# FPGA-ArduinoR3.net
KiCad netlist of a schematic drawn in EAGLE
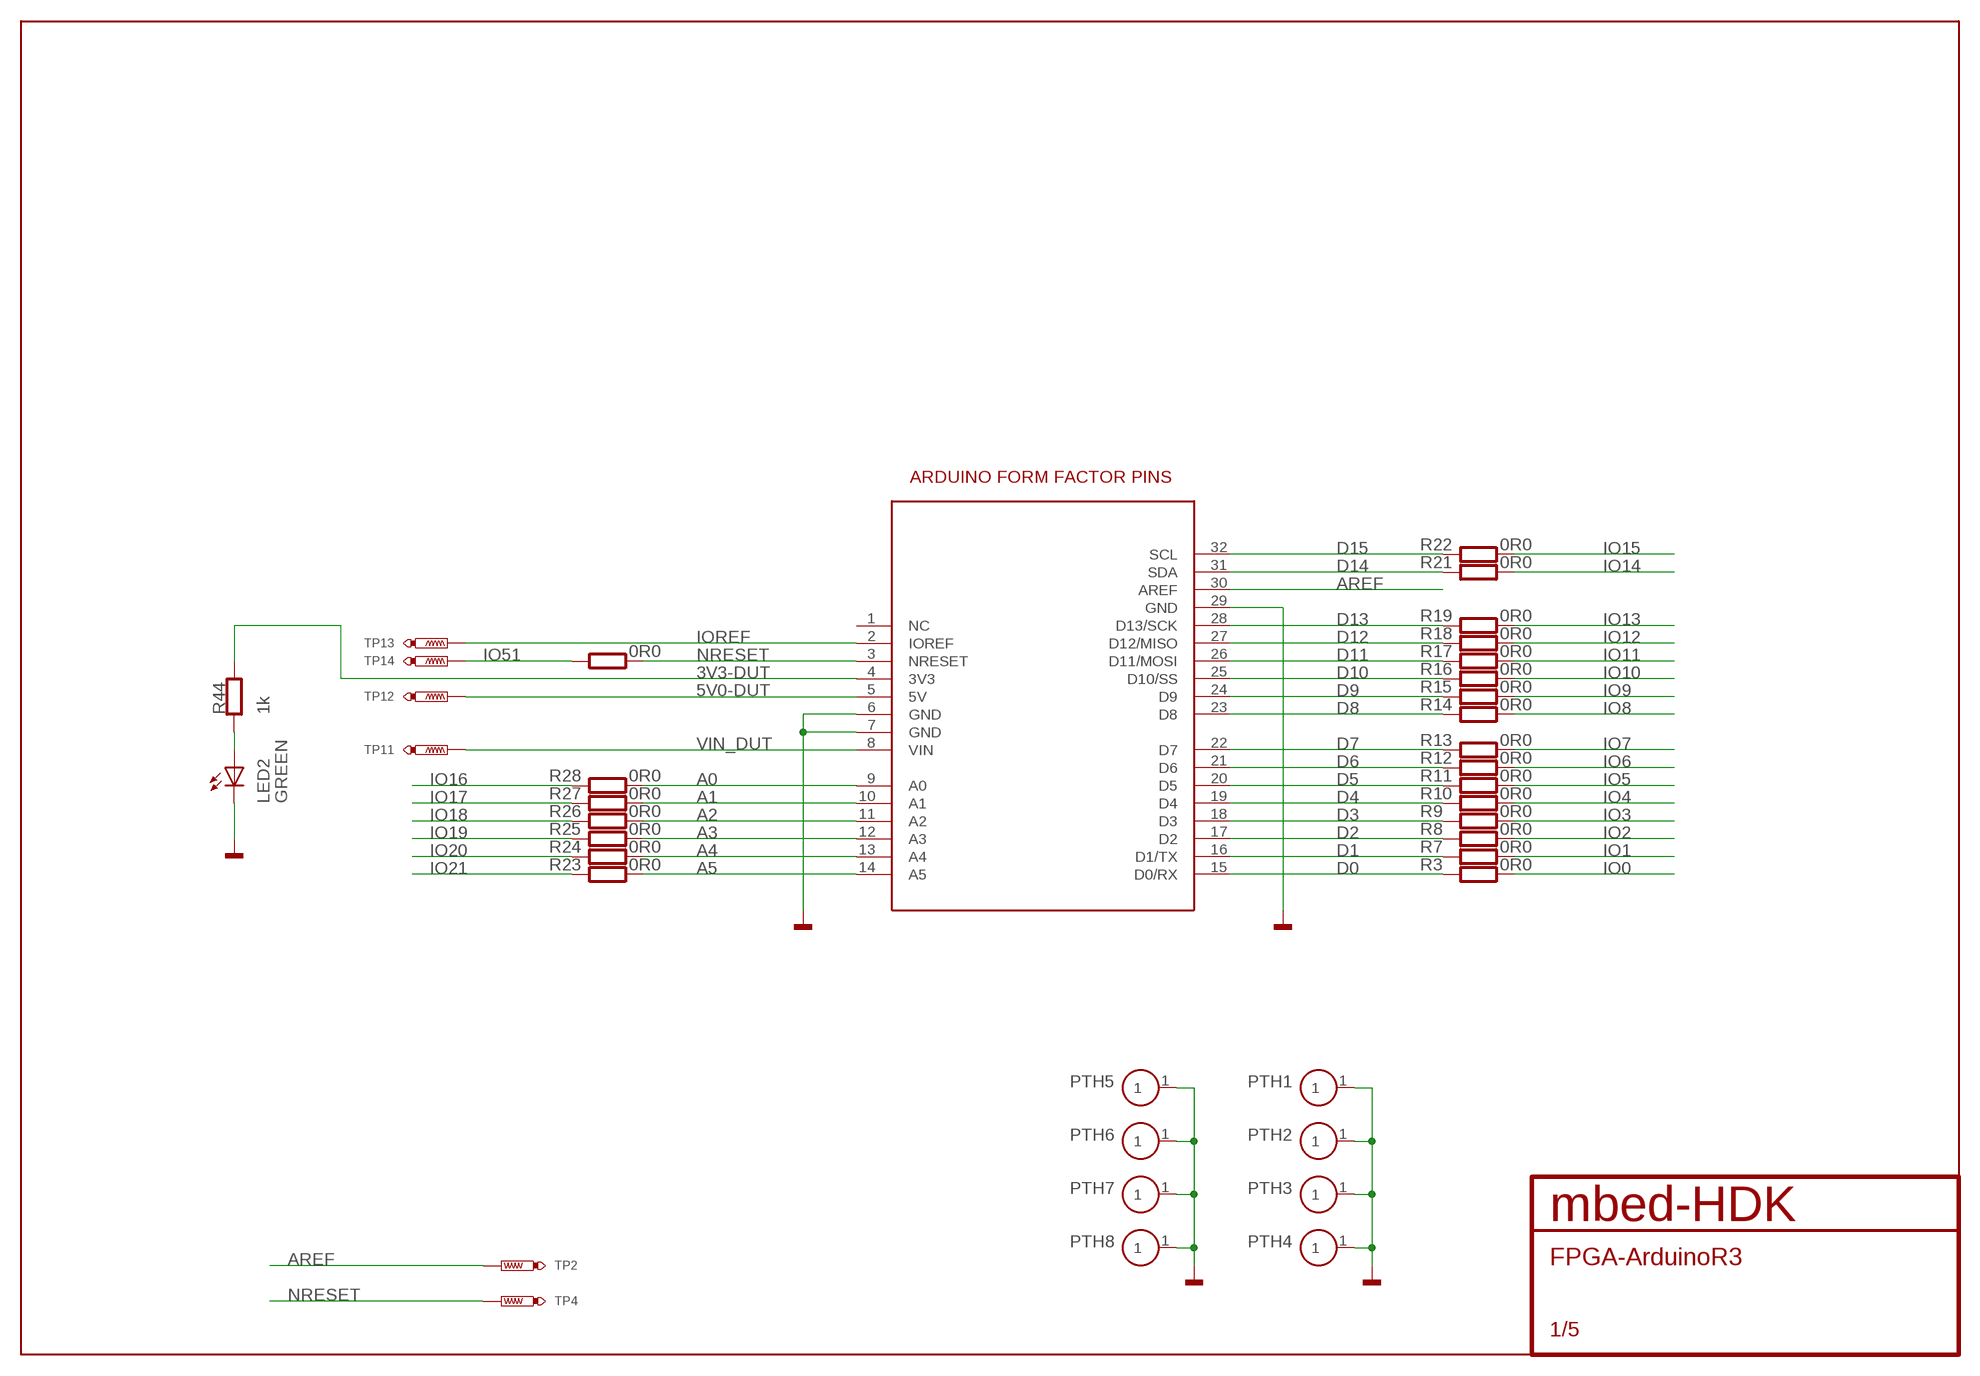
[diagram p0: schematic, sheet 1]
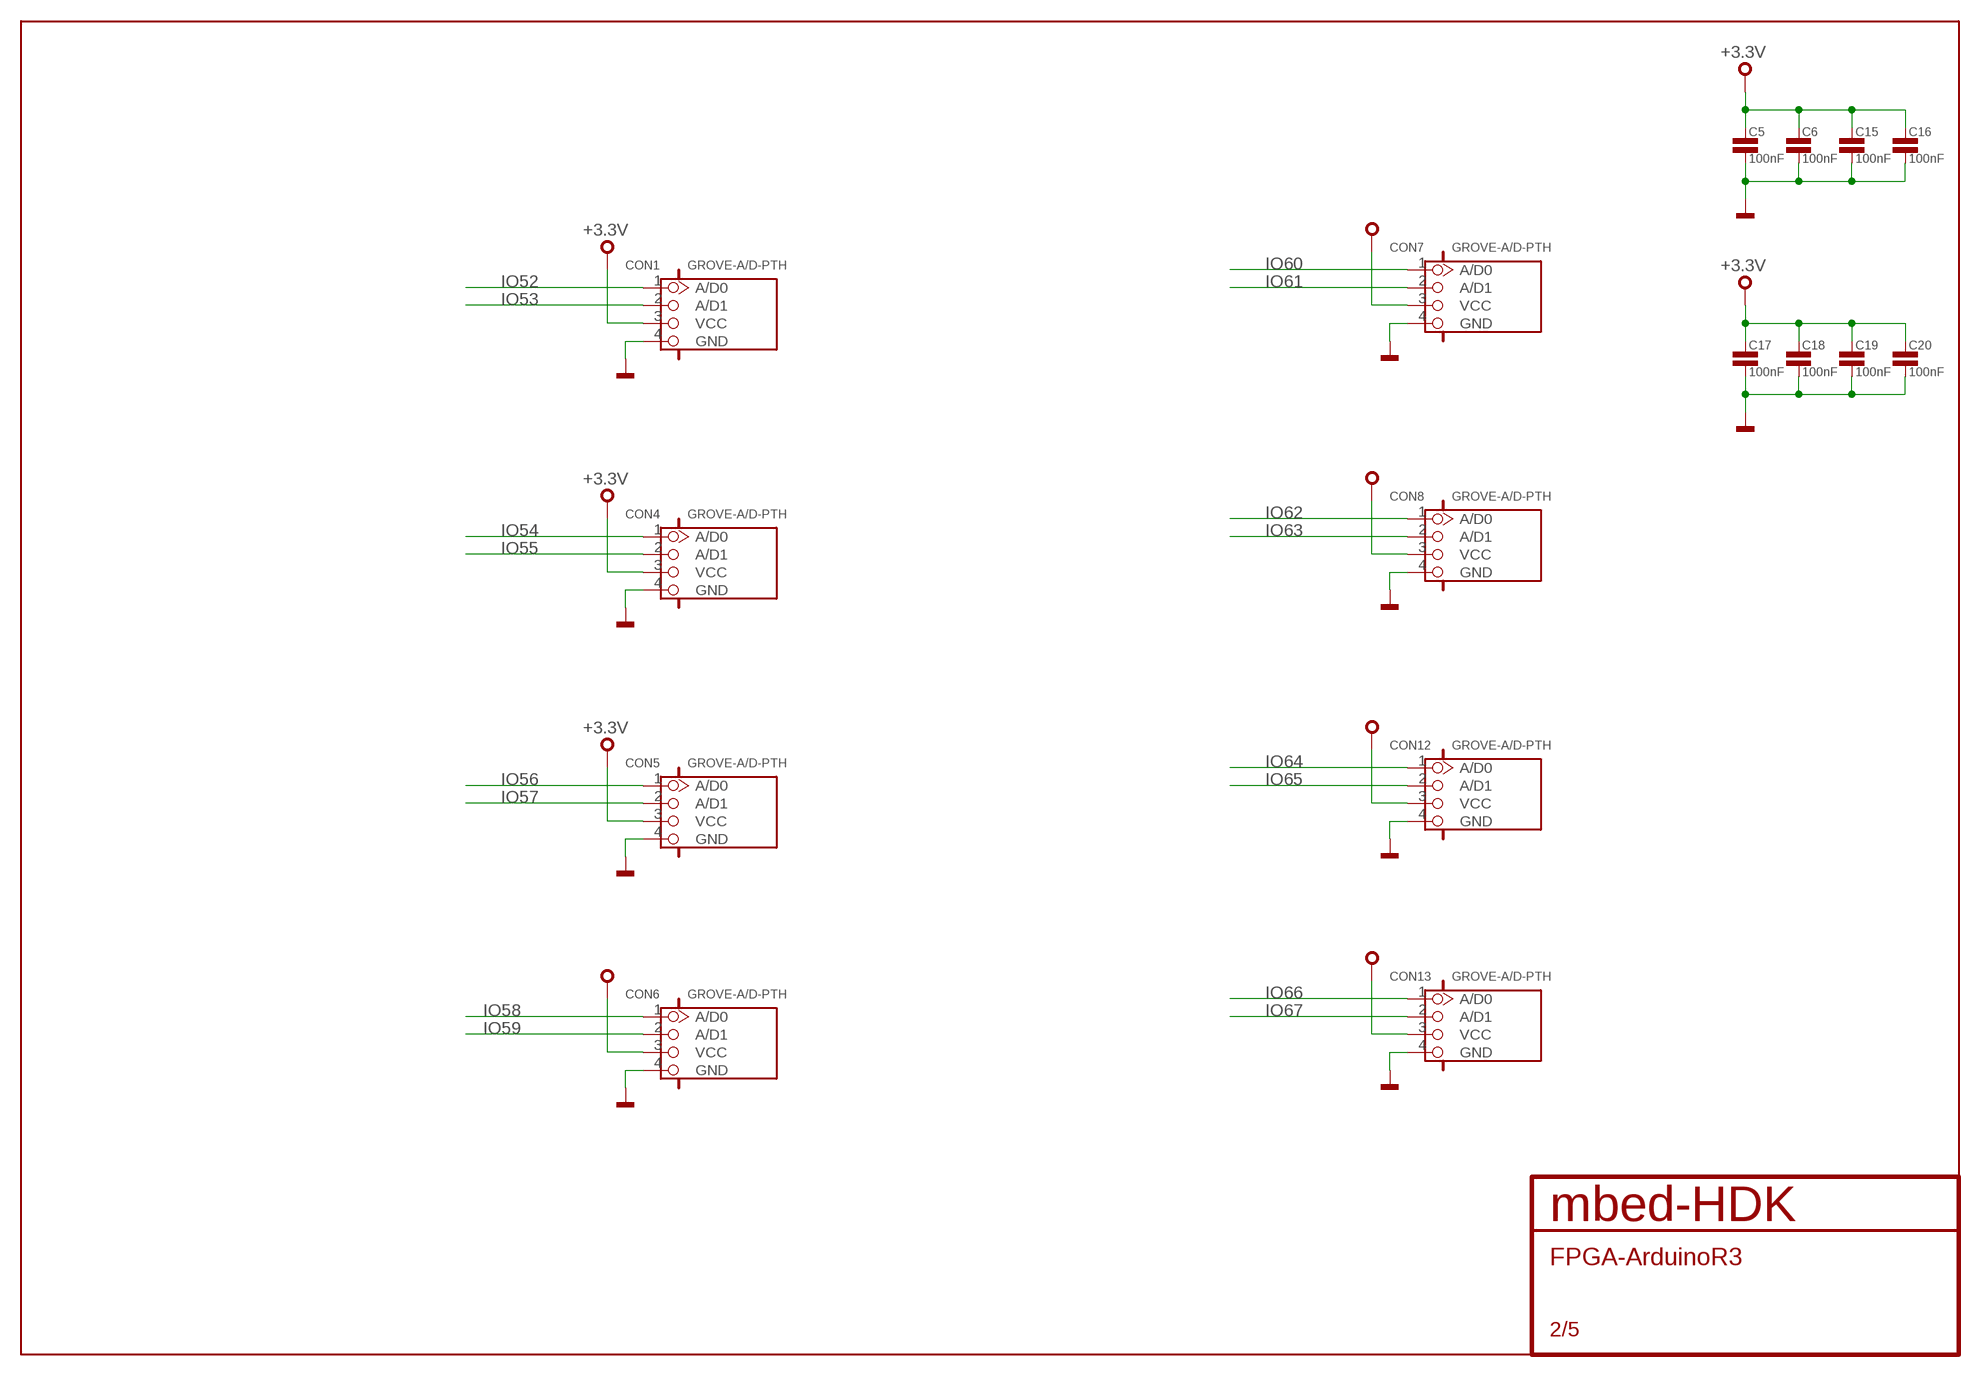
[diagram p1: schematic, sheet 2]
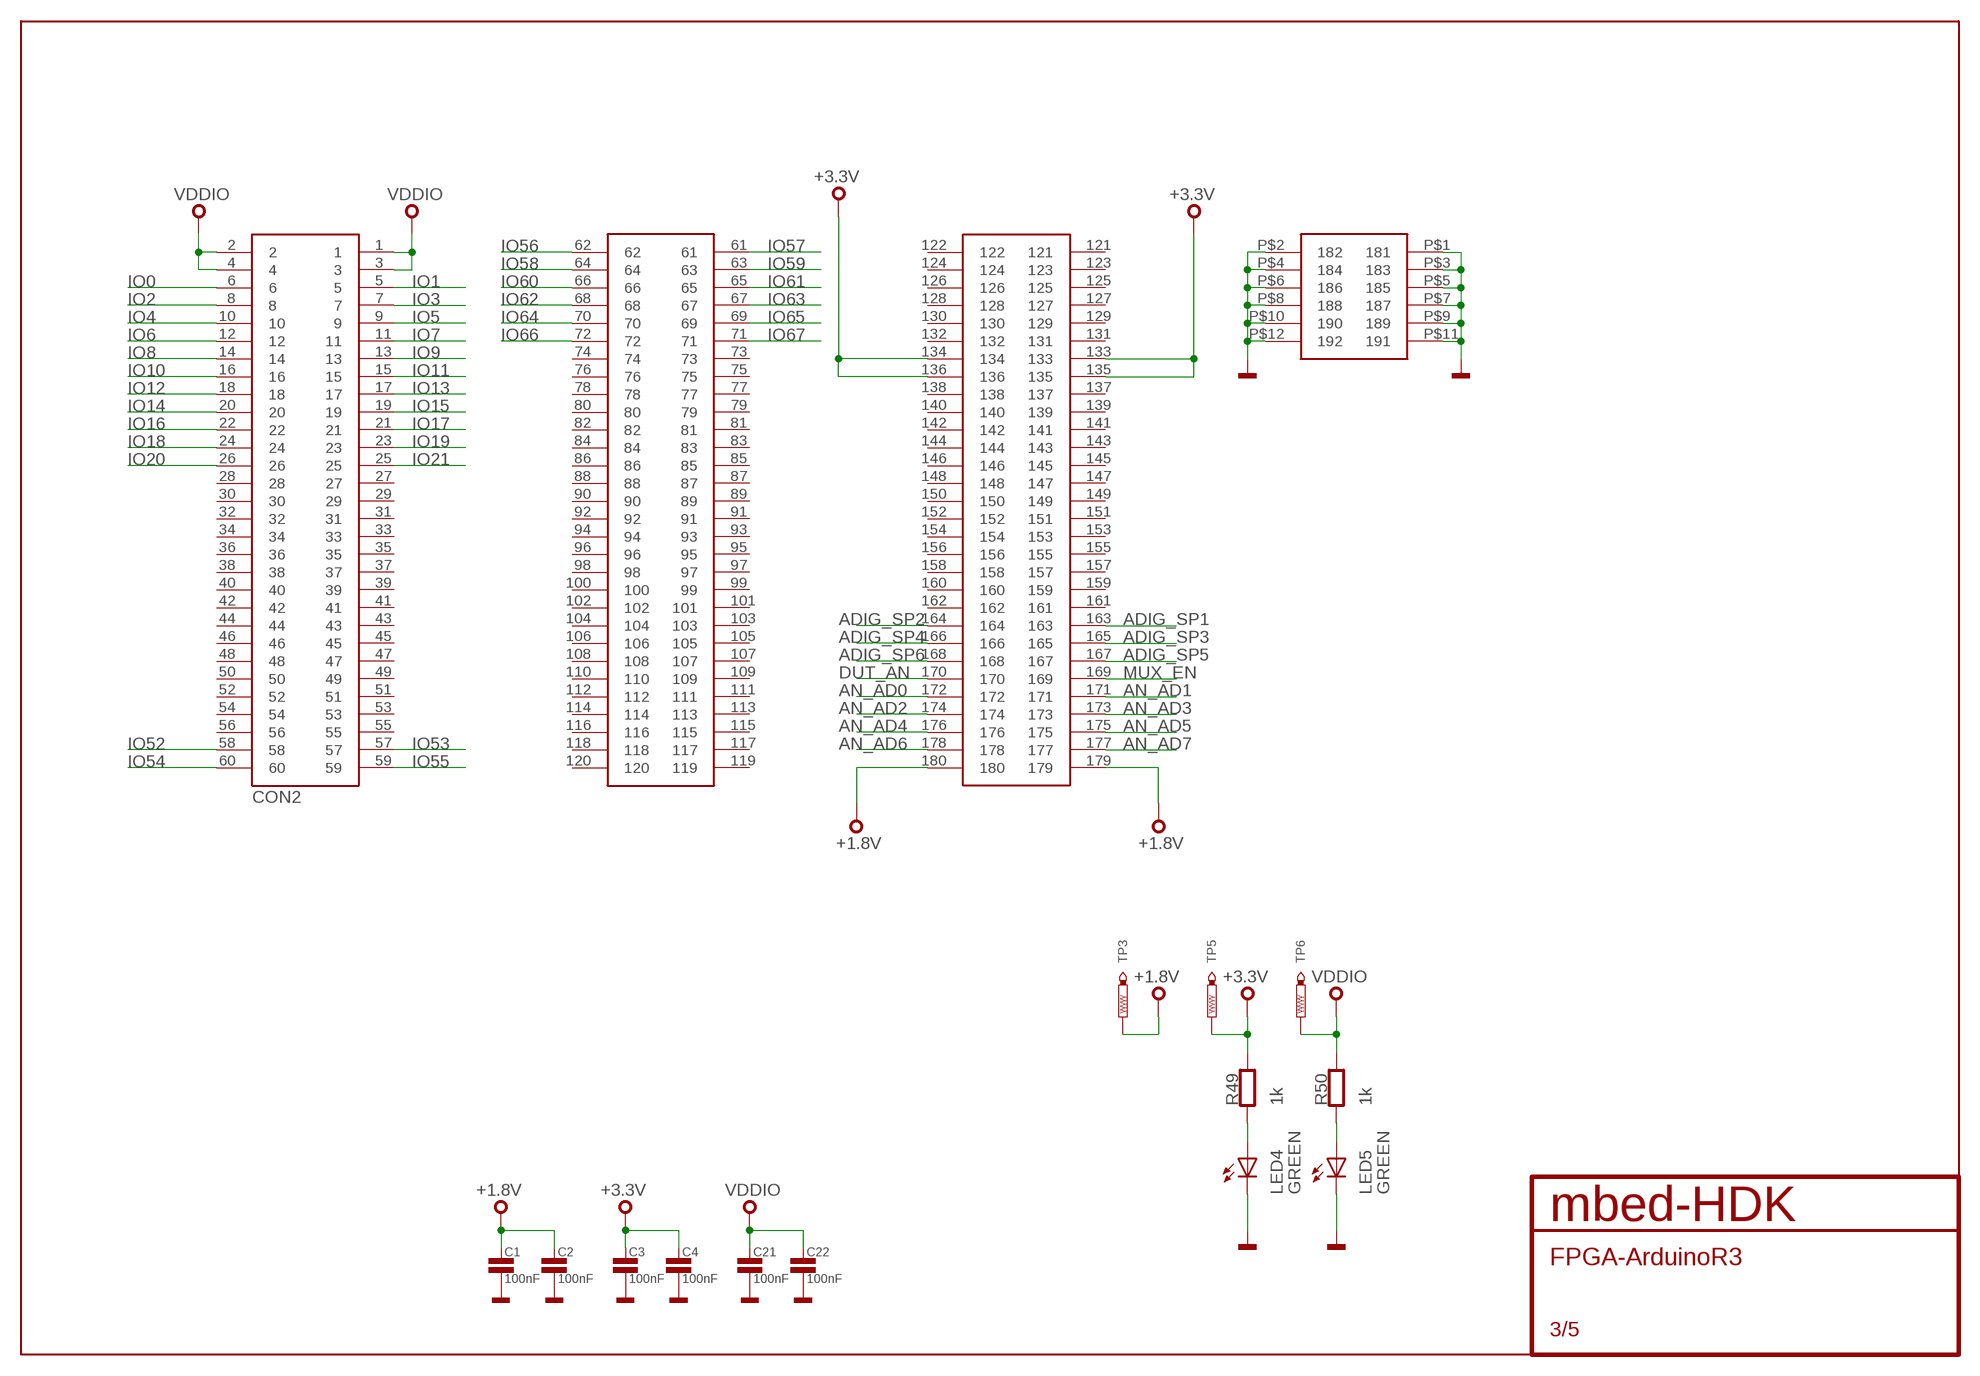
[diagram p2: schematic, sheet 3]
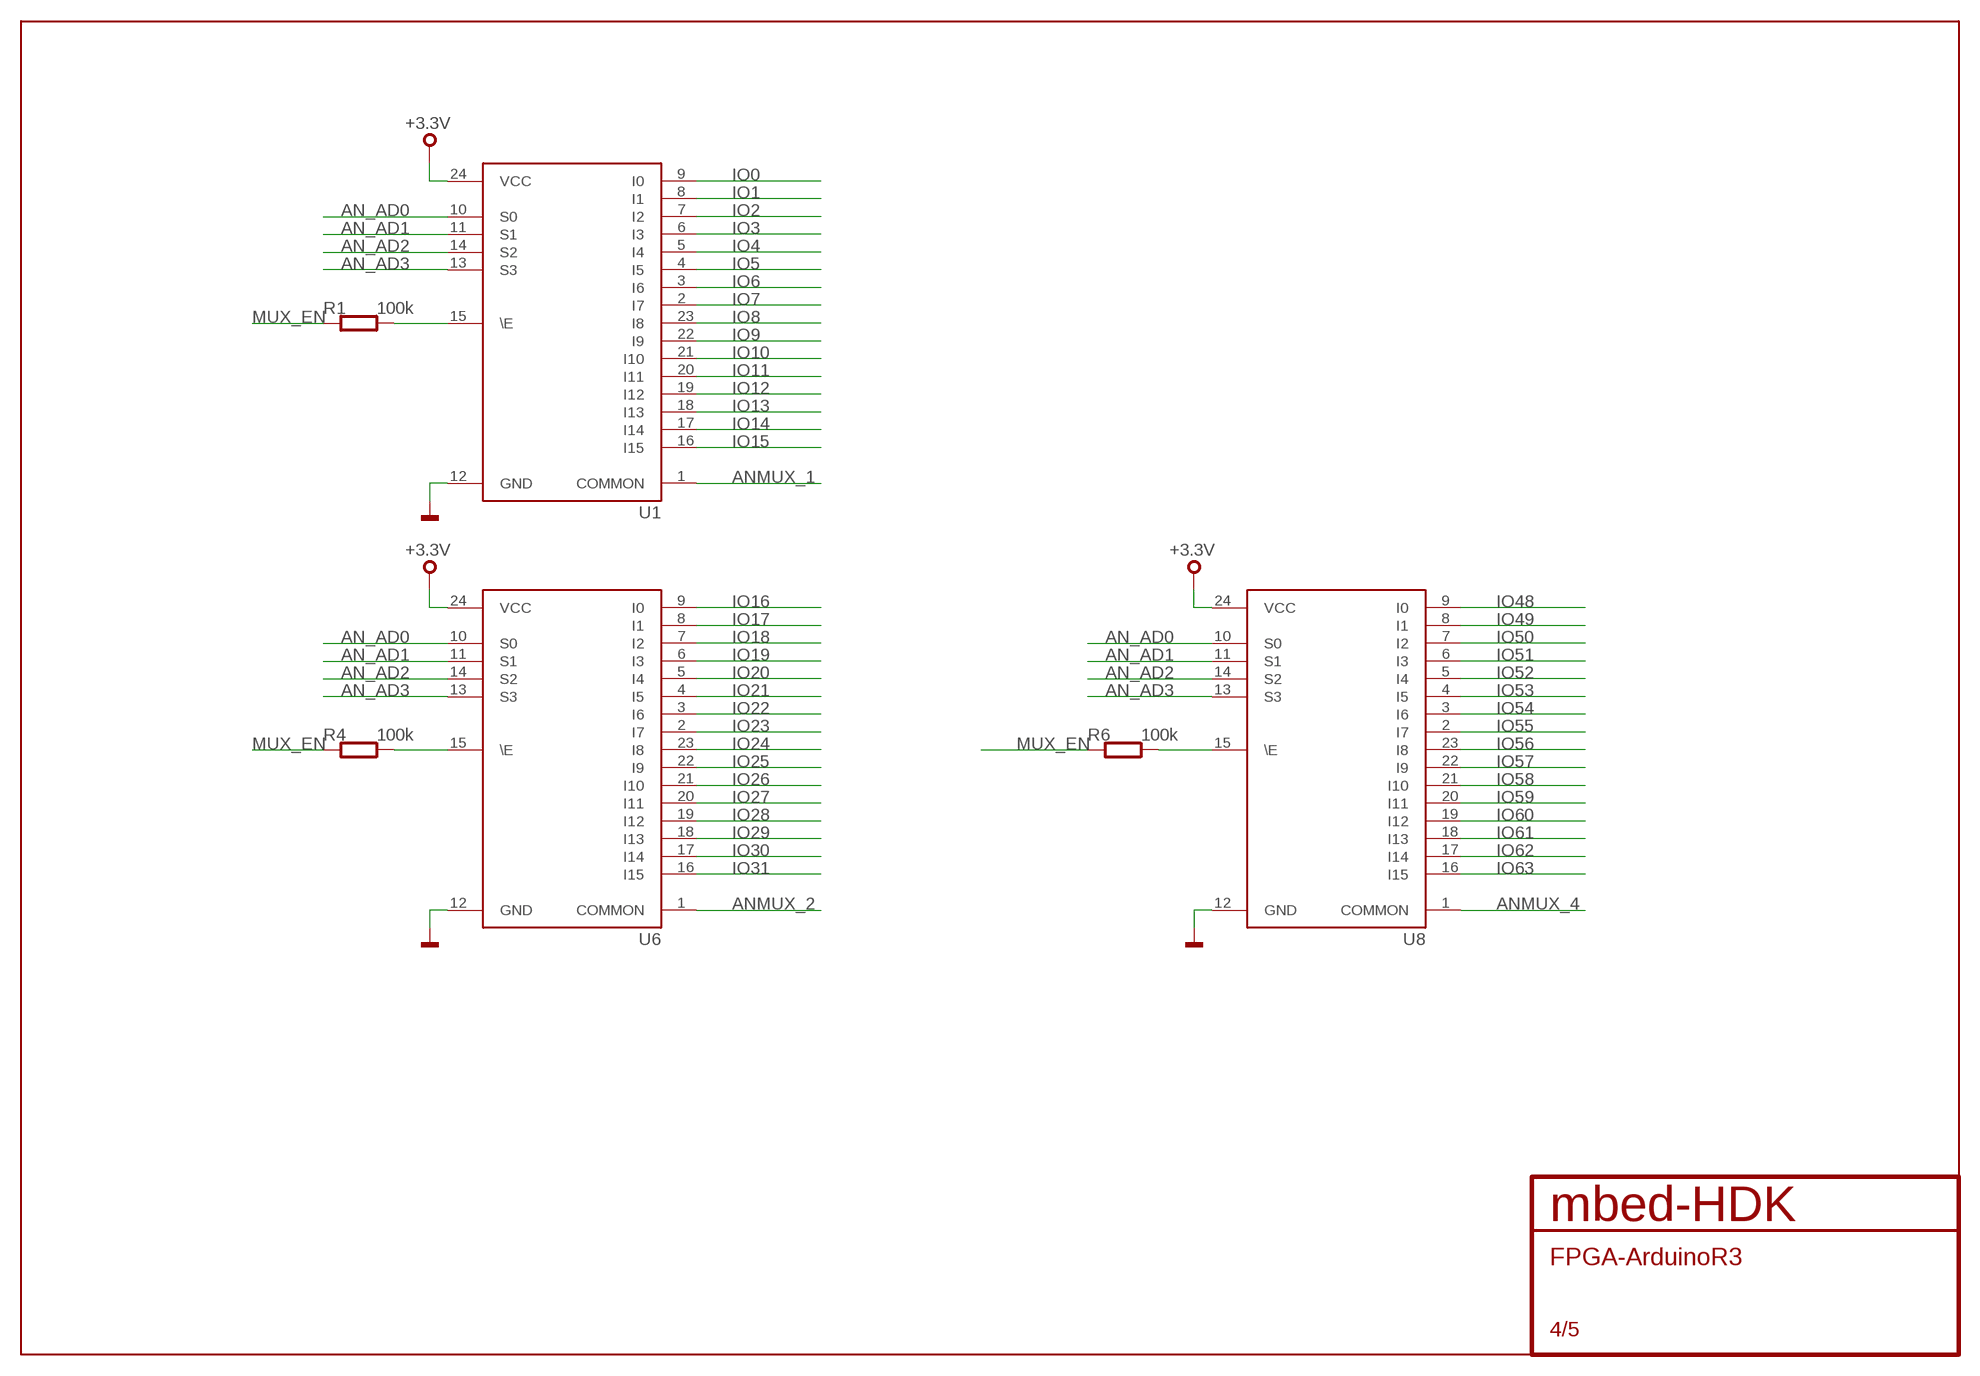
[diagram p3: schematic, sheet 4]
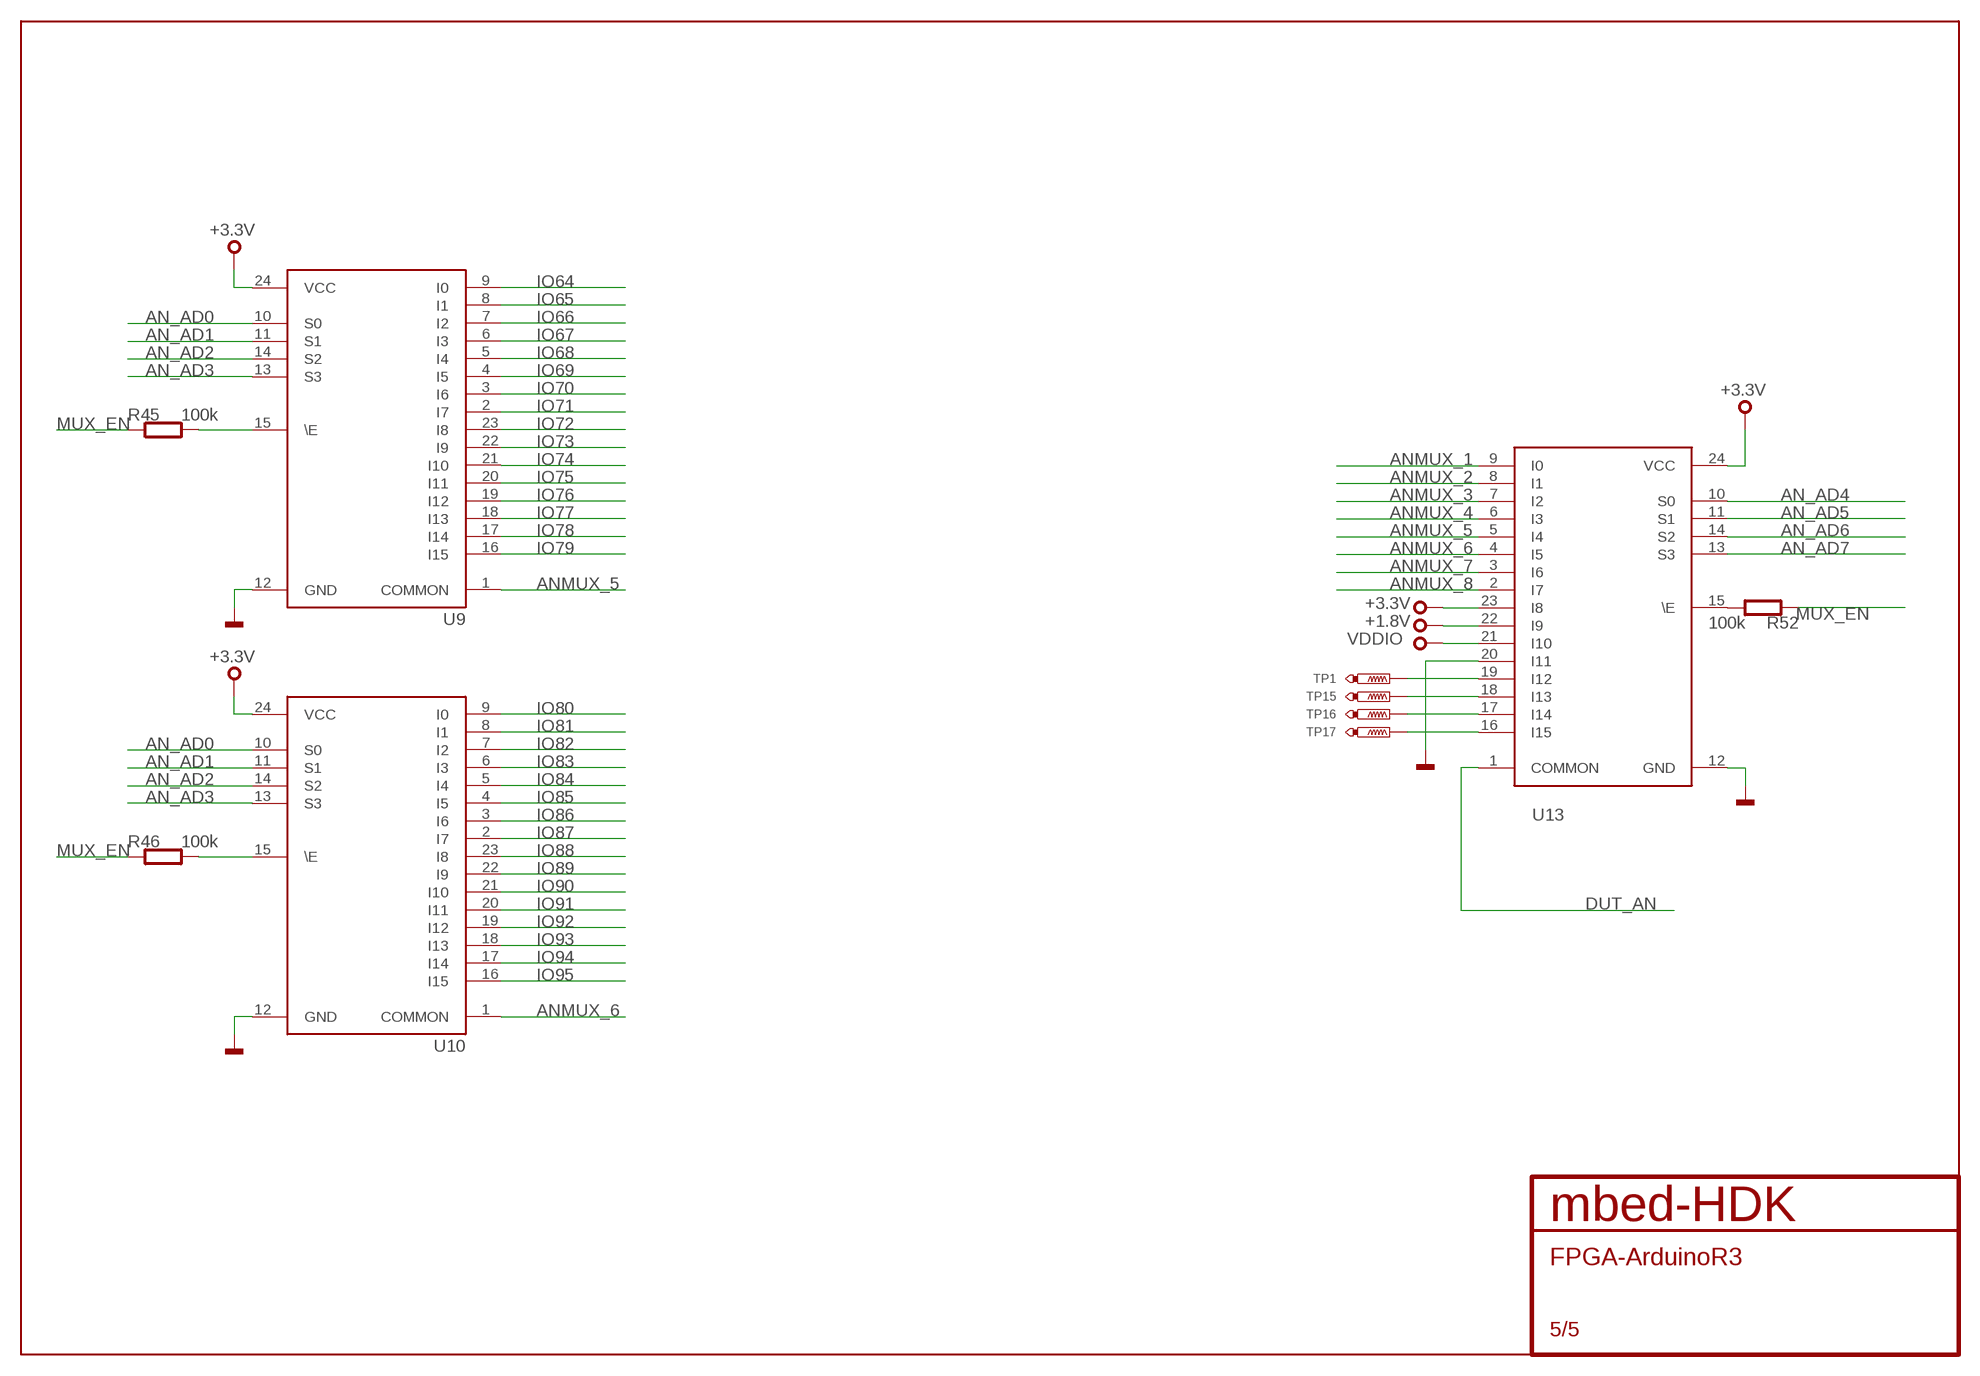
[diagram p4: schematic, sheet 5]

(export (version "E")
  (design (tool "Eeschema 10.0.6"))
  (components
    (comp (ref "R1")
      (value "100k")
      (footprint "eagle-import:0603")
      (libsource (lib "eagle-import") (part "R0603"))
    )
    (comp (ref "R4")
      (value "100k")
      (footprint "eagle-import:0603")
      (libsource (lib "eagle-import") (part "R0603"))
    )
    (comp (ref "R6")
      (value "100k")
      (footprint "eagle-import:0603")
      (libsource (lib "eagle-import") (part "R0603"))
    )
    (comp (ref "U1")
      (value "CD74HCT4067")
      (footprint "eagle-import:SO24")
      (libsource (lib "eagle-import") (part "CD74HCT4067"))
    )
    (comp (ref "U6")
      (value "CD74HCT4067")
      (footprint "eagle-import:SO24")
      (libsource (lib "eagle-import") (part "CD74HCT4067"))
    )
    (comp (ref "U8")
      (value "CD74HCT4067")
      (footprint "eagle-import:SO24")
      (libsource (lib "eagle-import") (part "CD74HCT4067"))
    )
    (comp (ref "C1")
      (value "100nF")
      (footprint "eagle-import:0603")
      (libsource (lib "eagle-import") (part "C0603"))
    )
    (comp (ref "C2")
      (value "100nF")
      (footprint "eagle-import:0603")
      (libsource (lib "eagle-import") (part "C0603"))
    )
    (comp (ref "C3")
      (value "100nF")
      (footprint "eagle-import:0603")
      (libsource (lib "eagle-import") (part "C0603"))
    )
    (comp (ref "C4")
      (value "100nF")
      (footprint "eagle-import:0603")
      (libsource (lib "eagle-import") (part "C0603"))
    )
    (comp (ref "C21")
      (value "100nF")
      (footprint "eagle-import:0603")
      (libsource (lib "eagle-import") (part "C0603"))
    )
    (comp (ref "C22")
      (value "100nF")
      (footprint "eagle-import:0603")
      (libsource (lib "eagle-import") (part "C0603"))
    )
    (comp (ref "CON2")
      (value "QSH-090-01-L-D-A")
      (footprint "eagle-import:QSH-090-01-L-D-A")
      (libsource (lib "eagle-import") (part "QSH-090-01-L-D-A"))
    )
    (comp (ref "LED4")
      (value "GREEN")
      (footprint "eagle-import:CHIPLED_0603")
      (libsource (lib "eagle-import") (part "LED0603"))
    )
    (comp (ref "LED5")
      (value "GREEN")
      (footprint "eagle-import:CHIPLED_0603")
      (libsource (lib "eagle-import") (part "LED0603"))
    )
    (comp (ref "R49")
      (value "1k")
      (footprint "eagle-import:0603")
      (libsource (lib "eagle-import") (part "R0603"))
    )
    (comp (ref "R50")
      (value "1k")
      (footprint "eagle-import:0603")
      (libsource (lib "eagle-import") (part "R0603"))
    )
    (comp (ref "TP3")
      (value "TEST_POINT-50R-PTH")
      (footprint "eagle-import:TP50-PTH")
      (libsource (lib "eagle-import") (part "TEST_POINT-50R-PTH"))
    )
    (comp (ref "TP5")
      (value "TEST_POINT-50R-PTH")
      (footprint "eagle-import:TP50-PTH")
      (libsource (lib "eagle-import") (part "TEST_POINT-50R-PTH"))
    )
    (comp (ref "TP6")
      (value "TEST_POINT-50R-PTH")
      (footprint "eagle-import:TP50-PTH")
      (libsource (lib "eagle-import") (part "TEST_POINT-50R-PTH"))
    )
    (comp (ref "C5")
      (value "100nF")
      (footprint "eagle-import:0603")
      (libsource (lib "eagle-import") (part "C0603"))
    )
    (comp (ref "C6")
      (value "100nF")
      (footprint "eagle-import:0603")
      (libsource (lib "eagle-import") (part "C0603"))
    )
    (comp (ref "C15")
      (value "100nF")
      (footprint "eagle-import:0603")
      (libsource (lib "eagle-import") (part "C0603"))
    )
    (comp (ref "C16")
      (value "100nF")
      (footprint "eagle-import:0603")
      (libsource (lib "eagle-import") (part "C0603"))
    )
    (comp (ref "C17")
      (value "100nF")
      (footprint "eagle-import:0603")
      (libsource (lib "eagle-import") (part "C0603"))
    )
    (comp (ref "C18")
      (value "100nF")
      (footprint "eagle-import:0603")
      (libsource (lib "eagle-import") (part "C0603"))
    )
    (comp (ref "C19")
      (value "100nF")
      (footprint "eagle-import:0603")
      (libsource (lib "eagle-import") (part "C0603"))
    )
    (comp (ref "C20")
      (value "100nF")
      (footprint "eagle-import:0603")
      (libsource (lib "eagle-import") (part "C0603"))
    )
    (comp (ref "CON1")
      (value "GROVE-A/D-PTH")
      (footprint "eagle-import:HW4-2.0")
      (libsource (lib "eagle-import") (part "GROVE-A/D-PTH"))
    )
    (comp (ref "CON4")
      (value "GROVE-A/D-PTH")
      (footprint "eagle-import:HW4-2.0")
      (libsource (lib "eagle-import") (part "GROVE-A/D-PTH"))
    )
    (comp (ref "CON5")
      (value "GROVE-A/D-PTH")
      (footprint "eagle-import:HW4-2.0")
      (libsource (lib "eagle-import") (part "GROVE-A/D-PTH"))
    )
    (comp (ref "CON6")
      (value "GROVE-A/D-PTH")
      (footprint "eagle-import:HW4-2.0")
      (libsource (lib "eagle-import") (part "GROVE-A/D-PTH"))
    )
    (comp (ref "CON7")
      (value "GROVE-A/D-PTH")
      (footprint "eagle-import:HW4-2.0")
      (libsource (lib "eagle-import") (part "GROVE-A/D-PTH"))
    )
    (comp (ref "CON8")
      (value "GROVE-A/D-PTH")
      (footprint "eagle-import:HW4-2.0")
      (libsource (lib "eagle-import") (part "GROVE-A/D-PTH"))
    )
    (comp (ref "CON12")
      (value "GROVE-A/D-PTH")
      (footprint "eagle-import:HW4-2.0")
      (libsource (lib "eagle-import") (part "GROVE-A/D-PTH"))
    )
    (comp (ref "CON13")
      (value "GROVE-A/D-PTH")
      (footprint "eagle-import:HW4-2.0")
      (libsource (lib "eagle-import") (part "GROVE-A/D-PTH"))
    )
    (comp (ref "R45")
      (value "100k")
      (footprint "eagle-import:0603")
      (libsource (lib "eagle-import") (part "R0603"))
    )
    (comp (ref "R46")
      (value "100k")
      (footprint "eagle-import:0603")
      (libsource (lib "eagle-import") (part "R0603"))
    )
    (comp (ref "R52")
      (value "100k")
      (footprint "eagle-import:0603")
      (libsource (lib "eagle-import") (part "R0603"))
    )
    (comp (ref "TP1")
      (value "TEST_POINT-50R-PTH")
      (footprint "eagle-import:TP50-PTH")
      (libsource (lib "eagle-import") (part "TEST_POINT-50R-PTH"))
    )
    (comp (ref "TP15")
      (value "TEST_POINT-50R-PTH")
      (footprint "eagle-import:TP50-PTH")
      (libsource (lib "eagle-import") (part "TEST_POINT-50R-PTH"))
    )
    (comp (ref "TP16")
      (value "TEST_POINT-50R-PTH")
      (footprint "eagle-import:TP50-PTH")
      (libsource (lib "eagle-import") (part "TEST_POINT-50R-PTH"))
    )
    (comp (ref "TP17")
      (value "TEST_POINT-50R-PTH")
      (footprint "eagle-import:TP50-PTH")
      (libsource (lib "eagle-import") (part "TEST_POINT-50R-PTH"))
    )
    (comp (ref "U9")
      (value "CD74HCT4067")
      (footprint "eagle-import:SO24")
      (libsource (lib "eagle-import") (part "CD74HCT4067"))
    )
    (comp (ref "U10")
      (value "CD74HCT4067")
      (footprint "eagle-import:SO24")
      (libsource (lib "eagle-import") (part "CD74HCT4067"))
    )
    (comp (ref "U13")
      (value "CD74HCT4067")
      (footprint "eagle-import:SO24")
      (libsource (lib "eagle-import") (part "CD74HCT4067"))
    )
    (comp (ref "BRD1")
      (value "ARDUINO-R3_SILK")
      (footprint "eagle-import:ARDUINO-R3-SILK")
      (libsource (lib "eagle-import") (part "ARDUINO-R3_SILK"))
    )
    (comp (ref "LED2")
      (value "GREEN")
      (footprint "eagle-import:CHIPLED_0603")
      (libsource (lib "eagle-import") (part "LED0603"))
    )
    (comp (ref "PTH1")
      (value "FIXINGHOLE")
      (footprint "eagle-import:PTH-140-300")
      (libsource (lib "eagle-import") (part "FIXINGHOLE"))
    )
    (comp (ref "PTH2")
      (value "FIXINGHOLE")
      (footprint "eagle-import:PTH-140-300")
      (libsource (lib "eagle-import") (part "FIXINGHOLE"))
    )
    (comp (ref "PTH3")
      (value "FIXINGHOLE")
      (footprint "eagle-import:PTH-140-300")
      (libsource (lib "eagle-import") (part "FIXINGHOLE"))
    )
    (comp (ref "PTH4")
      (value "FIXINGHOLE")
      (footprint "eagle-import:PTH-140-300")
      (libsource (lib "eagle-import") (part "FIXINGHOLE"))
    )
    (comp (ref "PTH5")
      (value "FIXINGHOLE")
      (footprint "eagle-import:PTH-140-300")
      (libsource (lib "eagle-import") (part "FIXINGHOLE"))
    )
    (comp (ref "PTH6")
      (value "FIXINGHOLE")
      (footprint "eagle-import:PTH-140-300")
      (libsource (lib "eagle-import") (part "FIXINGHOLE"))
    )
    (comp (ref "PTH7")
      (value "FIXINGHOLE")
      (footprint "eagle-import:PTH-140-300")
      (libsource (lib "eagle-import") (part "FIXINGHOLE"))
    )
    (comp (ref "PTH8")
      (value "FIXINGHOLE")
      (footprint "eagle-import:PTH-140-300")
      (libsource (lib "eagle-import") (part "FIXINGHOLE"))
    )
    (comp (ref "R2")
      (value "0R0")
      (footprint "eagle-import:0603")
      (libsource (lib "eagle-import") (part "R0603"))
    )
    (comp (ref "R3")
      (value "0R0")
      (footprint "eagle-import:0603")
      (libsource (lib "eagle-import") (part "R0603"))
    )
    (comp (ref "R7")
      (value "0R0")
      (footprint "eagle-import:0603")
      (libsource (lib "eagle-import") (part "R0603"))
    )
    (comp (ref "R8")
      (value "0R0")
      (footprint "eagle-import:0603")
      (libsource (lib "eagle-import") (part "R0603"))
    )
    (comp (ref "R9")
      (value "0R0")
      (footprint "eagle-import:0603")
      (libsource (lib "eagle-import") (part "R0603"))
    )
    (comp (ref "R10")
      (value "0R0")
      (footprint "eagle-import:0603")
      (libsource (lib "eagle-import") (part "R0603"))
    )
    (comp (ref "R11")
      (value "0R0")
      (footprint "eagle-import:0603")
      (libsource (lib "eagle-import") (part "R0603"))
    )
    (comp (ref "R12")
      (value "0R0")
      (footprint "eagle-import:0603")
      (libsource (lib "eagle-import") (part "R0603"))
    )
    (comp (ref "R13")
      (value "0R0")
      (footprint "eagle-import:0603")
      (libsource (lib "eagle-import") (part "R0603"))
    )
    (comp (ref "R14")
      (value "0R0")
      (footprint "eagle-import:0603")
      (libsource (lib "eagle-import") (part "R0603"))
    )
    (comp (ref "R15")
      (value "0R0")
      (footprint "eagle-import:0603")
      (libsource (lib "eagle-import") (part "R0603"))
    )
    (comp (ref "R16")
      (value "0R0")
      (footprint "eagle-import:0603")
      (libsource (lib "eagle-import") (part "R0603"))
    )
    (comp (ref "R17")
      (value "0R0")
      (footprint "eagle-import:0603")
      (libsource (lib "eagle-import") (part "R0603"))
    )
    (comp (ref "R18")
      (value "0R0")
      (footprint "eagle-import:0603")
      (libsource (lib "eagle-import") (part "R0603"))
    )
    (comp (ref "R19")
      (value "0R0")
      (footprint "eagle-import:0603")
      (libsource (lib "eagle-import") (part "R0603"))
    )
    (comp (ref "R21")
      (value "0R0")
      (footprint "eagle-import:0603")
      (libsource (lib "eagle-import") (part "R0603"))
    )
    (comp (ref "R22")
      (value "0R0")
      (footprint "eagle-import:0603")
      (libsource (lib "eagle-import") (part "R0603"))
    )
    (comp (ref "R23")
      (value "0R0")
      (footprint "eagle-import:0603")
      (libsource (lib "eagle-import") (part "R0603"))
    )
    (comp (ref "R24")
      (value "0R0")
      (footprint "eagle-import:0603")
      (libsource (lib "eagle-import") (part "R0603"))
    )
    (comp (ref "R25")
      (value "0R0")
      (footprint "eagle-import:0603")
      (libsource (lib "eagle-import") (part "R0603"))
    )
    (comp (ref "R26")
      (value "0R0")
      (footprint "eagle-import:0603")
      (libsource (lib "eagle-import") (part "R0603"))
    )
    (comp (ref "R27")
      (value "0R0")
      (footprint "eagle-import:0603")
      (libsource (lib "eagle-import") (part "R0603"))
    )
    (comp (ref "R28")
      (value "0R0")
      (footprint "eagle-import:0603")
      (libsource (lib "eagle-import") (part "R0603"))
    )
    (comp (ref "R44")
      (value "1k")
      (footprint "eagle-import:0603")
      (libsource (lib "eagle-import") (part "R0603"))
    )
    (comp (ref "TP2")
      (value "TEST_POINT-50R-SMD")
      (footprint "eagle-import:TP50-SMD")
      (libsource (lib "eagle-import") (part "TEST_POINT-50R-SMD"))
    )
    (comp (ref "TP4")
      (value "TEST_POINT-50R-SMD")
      (footprint "eagle-import:TP50-SMD")
      (libsource (lib "eagle-import") (part "TEST_POINT-50R-SMD"))
    )
    (comp (ref "TP11")
      (value "TEST_POINT-50R-SMD")
      (footprint "eagle-import:TP50-SMD")
      (libsource (lib "eagle-import") (part "TEST_POINT-50R-SMD"))
    )
    (comp (ref "TP12")
      (value "TEST_POINT-50R-SMD")
      (footprint "eagle-import:TP50-SMD")
      (libsource (lib "eagle-import") (part "TEST_POINT-50R-SMD"))
    )
    (comp (ref "TP13")
      (value "TEST_POINT-50R-SMD")
      (footprint "eagle-import:TP50-SMD")
      (libsource (lib "eagle-import") (part "TEST_POINT-50R-SMD"))
    )
    (comp (ref "TP14")
      (value "TEST_POINT-50R-SMD")
      (footprint "eagle-import:TP50-SMD")
      (libsource (lib "eagle-import") (part "TEST_POINT-50R-SMD"))
    )
  )
  (nets
    (net (code "1") (name "+1.8V") (class "Default")
      (node (ref "C1") (pin "1") (pinfunction "P$1_1") (pintype "passive"))
      (node (ref "C2") (pin "1") (pinfunction "P$1_1") (pintype "passive"))
      (node (ref "CON2") (pin "179") (pinfunction "179_179") (pintype "bidirectional"))
      (node (ref "CON2") (pin "180") (pinfunction "180_180") (pintype "bidirectional"))
      (node (ref "TP3") (pin "TP") (pinfunction "TP_TP") (pintype "input"))
      (node (ref "U13") (pin "22") (pinfunction "I9_22") (pintype "bidirectional"))
    )
    (net (code "2") (name "+3.3V") (class "Default")
      (node (ref "C15") (pin "1") (pinfunction "P$1_1") (pintype "passive"))
      (node (ref "C16") (pin "1") (pinfunction "P$1_1") (pintype "passive"))
      (node (ref "C17") (pin "1") (pinfunction "P$1_1") (pintype "passive"))
      (node (ref "C18") (pin "1") (pinfunction "P$1_1") (pintype "passive"))
      (node (ref "C19") (pin "1") (pinfunction "P$1_1") (pintype "passive"))
      (node (ref "C20") (pin "1") (pinfunction "P$1_1") (pintype "passive"))
      (node (ref "C3") (pin "1") (pinfunction "P$1_1") (pintype "passive"))
      (node (ref "C4") (pin "1") (pinfunction "P$1_1") (pintype "passive"))
      (node (ref "C5") (pin "1") (pinfunction "P$1_1") (pintype "passive"))
      (node (ref "C6") (pin "1") (pinfunction "P$1_1") (pintype "passive"))
      (node (ref "CON1") (pin "3") (pinfunction "VCC_3") (pintype "bidirectional"))
      (node (ref "CON12") (pin "3") (pinfunction "VCC_3") (pintype "bidirectional"))
      (node (ref "CON13") (pin "3") (pinfunction "VCC_3") (pintype "bidirectional"))
      (node (ref "CON2") (pin "133") (pinfunction "133_133") (pintype "bidirectional"))
      (node (ref "CON2") (pin "134") (pinfunction "134_134") (pintype "bidirectional"))
      (node (ref "CON2") (pin "135") (pinfunction "135_135") (pintype "bidirectional"))
      (node (ref "CON2") (pin "136") (pinfunction "136_136") (pintype "bidirectional"))
      (node (ref "CON4") (pin "3") (pinfunction "VCC_3") (pintype "bidirectional"))
      (node (ref "CON5") (pin "3") (pinfunction "VCC_3") (pintype "bidirectional"))
      (node (ref "CON6") (pin "3") (pinfunction "VCC_3") (pintype "bidirectional"))
      (node (ref "CON7") (pin "3") (pinfunction "VCC_3") (pintype "bidirectional"))
      (node (ref "CON8") (pin "3") (pinfunction "VCC_3") (pintype "bidirectional"))
      (node (ref "R49") (pin "2") (pinfunction "P$2_2") (pintype "passive"))
      (node (ref "TP5") (pin "TP") (pinfunction "TP_TP") (pintype "input"))
      (node (ref "U1") (pin "24") (pinfunction "VCC_24") (pintype "bidirectional"))
      (node (ref "U10") (pin "24") (pinfunction "VCC_24") (pintype "bidirectional"))
      (node (ref "U13") (pin "23") (pinfunction "I8_23") (pintype "bidirectional"))
      (node (ref "U13") (pin "24") (pinfunction "VCC_24") (pintype "bidirectional"))
      (node (ref "U6") (pin "24") (pinfunction "VCC_24") (pintype "bidirectional"))
      (node (ref "U8") (pin "24") (pinfunction "VCC_24") (pintype "bidirectional"))
      (node (ref "U9") (pin "24") (pinfunction "VCC_24") (pintype "bidirectional"))
    )
    (net (code "3") (name "3V3-DUT") (class "Default")
      (node (ref "BRD1") (pin "4") (pinfunction "3V3_4") (pintype "bidirectional"))
      (node (ref "R44") (pin "2") (pinfunction "P$2_2") (pintype "passive"))
    )
    (net (code "4") (name "5V0-DUT") (class "Default")
      (node (ref "BRD1") (pin "5") (pinfunction "5V_5") (pintype "bidirectional"))
      (node (ref "TP12") (pin "TP") (pinfunction "TP_TP") (pintype "input"))
    )
    (net (code "5") (name "A0") (class "Default")
      (node (ref "BRD1") (pin "9") (pinfunction "A0_9") (pintype "bidirectional"))
      (node (ref "R28") (pin "1") (pinfunction "P$1_1") (pintype "passive"))
    )
    (net (code "6") (name "A1") (class "Default")
      (node (ref "BRD1") (pin "10") (pinfunction "A1_10") (pintype "bidirectional"))
      (node (ref "R27") (pin "1") (pinfunction "P$1_1") (pintype "passive"))
    )
    (net (code "7") (name "A2") (class "Default")
      (node (ref "BRD1") (pin "11") (pinfunction "A2_11") (pintype "bidirectional"))
      (node (ref "R26") (pin "1") (pinfunction "P$1_1") (pintype "passive"))
    )
    (net (code "8") (name "A3") (class "Default")
      (node (ref "BRD1") (pin "12") (pinfunction "A3_12") (pintype "bidirectional"))
      (node (ref "R25") (pin "1") (pinfunction "P$1_1") (pintype "passive"))
    )
    (net (code "9") (name "A4") (class "Default")
      (node (ref "BRD1") (pin "13") (pinfunction "A4_13") (pintype "bidirectional"))
      (node (ref "R24") (pin "1") (pinfunction "P$1_1") (pintype "passive"))
    )
    (net (code "10") (name "A5") (class "Default")
      (node (ref "BRD1") (pin "14") (pinfunction "A5_14") (pintype "bidirectional"))
      (node (ref "R23") (pin "1") (pinfunction "P$1_1") (pintype "passive"))
    )
    (net (code "11") (name "ADIG_SP1") (class "Default")
      (node (ref "CON2") (pin "163") (pinfunction "163_163") (pintype "bidirectional"))
    )
    (net (code "12") (name "ADIG_SP2") (class "Default")
      (node (ref "CON2") (pin "164") (pinfunction "164_164") (pintype "bidirectional"))
    )
    (net (code "13") (name "ADIG_SP3") (class "Default")
      (node (ref "CON2") (pin "165") (pinfunction "165_165") (pintype "bidirectional"))
    )
    (net (code "14") (name "ADIG_SP4") (class "Default")
      (node (ref "CON2") (pin "166") (pinfunction "166_166") (pintype "bidirectional"))
    )
    (net (code "15") (name "ADIG_SP5") (class "Default")
      (node (ref "CON2") (pin "167") (pinfunction "167_167") (pintype "bidirectional"))
    )
    (net (code "16") (name "ADIG_SP6") (class "Default")
      (node (ref "CON2") (pin "168") (pinfunction "168_168") (pintype "bidirectional"))
    )
    (net (code "17") (name "ANMUX_1") (class "Default")
      (node (ref "U1") (pin "1") (pinfunction "COMMON_1") (pintype "bidirectional"))
      (node (ref "U13") (pin "9") (pinfunction "I0_9") (pintype "bidirectional"))
    )
    (net (code "18") (name "ANMUX_2") (class "Default")
      (node (ref "U13") (pin "8") (pinfunction "I1_8") (pintype "bidirectional"))
      (node (ref "U6") (pin "1") (pinfunction "COMMON_1") (pintype "bidirectional"))
    )
    (net (code "19") (name "ANMUX_3") (class "Default")
      (node (ref "U13") (pin "7") (pinfunction "I2_7") (pintype "bidirectional"))
    )
    (net (code "20") (name "ANMUX_4") (class "Default")
      (node (ref "U13") (pin "6") (pinfunction "I3_6") (pintype "bidirectional"))
      (node (ref "U8") (pin "1") (pinfunction "COMMON_1") (pintype "bidirectional"))
    )
    (net (code "21") (name "ANMUX_5") (class "Default")
      (node (ref "U13") (pin "5") (pinfunction "I4_5") (pintype "bidirectional"))
      (node (ref "U9") (pin "1") (pinfunction "COMMON_1") (pintype "bidirectional"))
    )
    (net (code "22") (name "ANMUX_6") (class "Default")
      (node (ref "U10") (pin "1") (pinfunction "COMMON_1") (pintype "bidirectional"))
      (node (ref "U13") (pin "4") (pinfunction "I5_4") (pintype "bidirectional"))
    )
    (net (code "23") (name "ANMUX_7") (class "Default")
      (node (ref "U13") (pin "3") (pinfunction "I6_3") (pintype "bidirectional"))
    )
    (net (code "24") (name "ANMUX_8") (class "Default")
      (node (ref "U13") (pin "2") (pinfunction "I7_2") (pintype "bidirectional"))
    )
    (net (code "25") (name "AN_AD0") (class "Default")
      (node (ref "CON2") (pin "172") (pinfunction "172_172") (pintype "bidirectional"))
      (node (ref "U1") (pin "10") (pinfunction "S0_10") (pintype "bidirectional"))
      (node (ref "U10") (pin "10") (pinfunction "S0_10") (pintype "bidirectional"))
      (node (ref "U6") (pin "10") (pinfunction "S0_10") (pintype "bidirectional"))
      (node (ref "U8") (pin "10") (pinfunction "S0_10") (pintype "bidirectional"))
      (node (ref "U9") (pin "10") (pinfunction "S0_10") (pintype "bidirectional"))
    )
    (net (code "26") (name "AN_AD1") (class "Default")
      (node (ref "CON2") (pin "171") (pinfunction "171_171") (pintype "bidirectional"))
      (node (ref "U1") (pin "11") (pinfunction "S1_11") (pintype "bidirectional"))
      (node (ref "U10") (pin "11") (pinfunction "S1_11") (pintype "bidirectional"))
      (node (ref "U6") (pin "11") (pinfunction "S1_11") (pintype "bidirectional"))
      (node (ref "U8") (pin "11") (pinfunction "S1_11") (pintype "bidirectional"))
      (node (ref "U9") (pin "11") (pinfunction "S1_11") (pintype "bidirectional"))
    )
    (net (code "27") (name "AN_AD2") (class "Default")
      (node (ref "CON2") (pin "174") (pinfunction "174_174") (pintype "bidirectional"))
      (node (ref "U1") (pin "14") (pinfunction "S2_14") (pintype "bidirectional"))
      (node (ref "U10") (pin "14") (pinfunction "S2_14") (pintype "bidirectional"))
      (node (ref "U6") (pin "14") (pinfunction "S2_14") (pintype "bidirectional"))
      (node (ref "U8") (pin "14") (pinfunction "S2_14") (pintype "bidirectional"))
      (node (ref "U9") (pin "14") (pinfunction "S2_14") (pintype "bidirectional"))
    )
    (net (code "28") (name "AN_AD3") (class "Default")
      (node (ref "CON2") (pin "173") (pinfunction "173_173") (pintype "bidirectional"))
      (node (ref "U1") (pin "13") (pinfunction "S3_13") (pintype "bidirectional"))
      (node (ref "U10") (pin "13") (pinfunction "S3_13") (pintype "bidirectional"))
      (node (ref "U6") (pin "13") (pinfunction "S3_13") (pintype "bidirectional"))
      (node (ref "U8") (pin "13") (pinfunction "S3_13") (pintype "bidirectional"))
      (node (ref "U9") (pin "13") (pinfunction "S3_13") (pintype "bidirectional"))
    )
    (net (code "29") (name "AN_AD4") (class "Default")
      (node (ref "CON2") (pin "176") (pinfunction "176_176") (pintype "bidirectional"))
      (node (ref "U13") (pin "10") (pinfunction "S0_10") (pintype "bidirectional"))
    )
    (net (code "30") (name "AN_AD5") (class "Default")
      (node (ref "CON2") (pin "175") (pinfunction "175_175") (pintype "bidirectional"))
      (node (ref "U13") (pin "11") (pinfunction "S1_11") (pintype "bidirectional"))
    )
    (net (code "31") (name "AN_AD6") (class "Default")
      (node (ref "CON2") (pin "178") (pinfunction "178_178") (pintype "bidirectional"))
      (node (ref "U13") (pin "14") (pinfunction "S2_14") (pintype "bidirectional"))
    )
    (net (code "32") (name "AN_AD7") (class "Default")
      (node (ref "CON2") (pin "177") (pinfunction "177_177") (pintype "bidirectional"))
      (node (ref "U13") (pin "13") (pinfunction "S3_13") (pintype "bidirectional"))
    )
    (net (code "33") (name "AREF") (class "Default")
      (node (ref "BRD1") (pin "30") (pinfunction "AREF_30") (pintype "bidirectional"))
      (node (ref "TP2") (pin "TP") (pinfunction "TP_TP") (pintype "input"))
    )
    (net (code "34") (name "D0") (class "Default")
      (node (ref "BRD1") (pin "15") (pinfunction "D0/RX_15") (pintype "bidirectional"))
      (node (ref "R3") (pin "2") (pinfunction "P$2_2") (pintype "passive"))
    )
    (net (code "35") (name "D1") (class "Default")
      (node (ref "BRD1") (pin "16") (pinfunction "D1/TX_16") (pintype "bidirectional"))
      (node (ref "R7") (pin "2") (pinfunction "P$2_2") (pintype "passive"))
    )
    (net (code "36") (name "D2") (class "Default")
      (node (ref "BRD1") (pin "17") (pinfunction "D2_17") (pintype "bidirectional"))
      (node (ref "R8") (pin "2") (pinfunction "P$2_2") (pintype "passive"))
    )
    (net (code "37") (name "D3") (class "Default")
      (node (ref "BRD1") (pin "18") (pinfunction "D3_18") (pintype "bidirectional"))
      (node (ref "R9") (pin "2") (pinfunction "P$2_2") (pintype "passive"))
    )
    (net (code "38") (name "D4") (class "Default")
      (node (ref "BRD1") (pin "19") (pinfunction "D4_19") (pintype "bidirectional"))
      (node (ref "R10") (pin "2") (pinfunction "P$2_2") (pintype "passive"))
    )
    (net (code "39") (name "D5") (class "Default")
      (node (ref "BRD1") (pin "20") (pinfunction "D5_20") (pintype "bidirectional"))
      (node (ref "R11") (pin "2") (pinfunction "P$2_2") (pintype "passive"))
    )
    (net (code "40") (name "D6") (class "Default")
      (node (ref "BRD1") (pin "21") (pinfunction "D6_21") (pintype "bidirectional"))
      (node (ref "R12") (pin "2") (pinfunction "P$2_2") (pintype "passive"))
    )
    (net (code "41") (name "D7") (class "Default")
      (node (ref "BRD1") (pin "22") (pinfunction "D7_22") (pintype "bidirectional"))
      (node (ref "R13") (pin "2") (pinfunction "P$2_2") (pintype "passive"))
    )
    (net (code "42") (name "D8") (class "Default")
      (node (ref "BRD1") (pin "23") (pinfunction "D8_23") (pintype "bidirectional"))
      (node (ref "R14") (pin "2") (pinfunction "P$2_2") (pintype "passive"))
    )
    (net (code "43") (name "D9") (class "Default")
      (node (ref "BRD1") (pin "24") (pinfunction "D9_24") (pintype "bidirectional"))
      (node (ref "R15") (pin "2") (pinfunction "P$2_2") (pintype "passive"))
    )
    (net (code "44") (name "D10") (class "Default")
      (node (ref "BRD1") (pin "25") (pinfunction "D10/SS_25") (pintype "bidirectional"))
      (node (ref "R16") (pin "2") (pinfunction "P$2_2") (pintype "passive"))
    )
    (net (code "45") (name "D11") (class "Default")
      (node (ref "BRD1") (pin "26") (pinfunction "D11/MOSI_26") (pintype "bidirectional"))
      (node (ref "R17") (pin "2") (pinfunction "P$2_2") (pintype "passive"))
    )
    (net (code "46") (name "D12") (class "Default")
      (node (ref "BRD1") (pin "27") (pinfunction "D12/MISO_27") (pintype "bidirectional"))
      (node (ref "R18") (pin "2") (pinfunction "P$2_2") (pintype "passive"))
    )
    (net (code "47") (name "D13") (class "Default")
      (node (ref "BRD1") (pin "28") (pinfunction "D13/SCK_28") (pintype "bidirectional"))
      (node (ref "R19") (pin "2") (pinfunction "P$2_2") (pintype "passive"))
    )
    (net (code "48") (name "D14") (class "Default")
      (node (ref "BRD1") (pin "31") (pinfunction "SDA_31") (pintype "bidirectional"))
      (node (ref "R21") (pin "2") (pinfunction "P$2_2") (pintype "passive"))
    )
    (net (code "49") (name "D15") (class "Default")
      (node (ref "BRD1") (pin "32") (pinfunction "SCL_32") (pintype "bidirectional"))
      (node (ref "R22") (pin "2") (pinfunction "P$2_2") (pintype "passive"))
    )
    (net (code "50") (name "DUT_AN") (class "Default")
      (node (ref "CON2") (pin "170") (pinfunction "170_170") (pintype "bidirectional"))
      (node (ref "U13") (pin "1") (pinfunction "COMMON_1") (pintype "bidirectional"))
    )
    (net (code "51") (name "GND") (class "Default")
      (node (ref "BRD1") (pin "29") (pinfunction "GND_29") (pintype "bidirectional"))
      (node (ref "BRD1") (pin "6") (pinfunction "GND_6") (pintype "bidirectional"))
      (node (ref "BRD1") (pin "7") (pinfunction "GND_7") (pintype "bidirectional"))
      (node (ref "C1") (pin "2") (pinfunction "P$2_2") (pintype "passive"))
      (node (ref "C15") (pin "2") (pinfunction "P$2_2") (pintype "passive"))
      (node (ref "C16") (pin "2") (pinfunction "P$2_2") (pintype "passive"))
      (node (ref "C17") (pin "2") (pinfunction "P$2_2") (pintype "passive"))
      (node (ref "C18") (pin "2") (pinfunction "P$2_2") (pintype "passive"))
      (node (ref "C19") (pin "2") (pinfunction "P$2_2") (pintype "passive"))
      (node (ref "C2") (pin "2") (pinfunction "P$2_2") (pintype "passive"))
      (node (ref "C20") (pin "2") (pinfunction "P$2_2") (pintype "passive"))
      (node (ref "C21") (pin "2") (pinfunction "P$2_2") (pintype "passive"))
      (node (ref "C22") (pin "2") (pinfunction "P$2_2") (pintype "passive"))
      (node (ref "C3") (pin "2") (pinfunction "P$2_2") (pintype "passive"))
      (node (ref "C4") (pin "2") (pinfunction "P$2_2") (pintype "passive"))
      (node (ref "C5") (pin "2") (pinfunction "P$2_2") (pintype "passive"))
      (node (ref "C6") (pin "2") (pinfunction "P$2_2") (pintype "passive"))
      (node (ref "CON1") (pin "4") (pinfunction "GND_4") (pintype "bidirectional"))
      (node (ref "CON12") (pin "4") (pinfunction "GND_4") (pintype "bidirectional"))
      (node (ref "CON13") (pin "4") (pinfunction "GND_4") (pintype "bidirectional"))
      (node (ref "CON2") (pin "P$1") (pinfunction "181_P$1") (pintype "bidirectional"))
      (node (ref "CON2") (pin "P$10") (pinfunction "190_P$10") (pintype "bidirectional"))
      (node (ref "CON2") (pin "P$11") (pinfunction "191_P$11") (pintype "bidirectional"))
      (node (ref "CON2") (pin "P$12") (pinfunction "192_P$12") (pintype "bidirectional"))
      (node (ref "CON2") (pin "P$2") (pinfunction "182_P$2") (pintype "bidirectional"))
      (node (ref "CON2") (pin "P$3") (pinfunction "183_P$3") (pintype "bidirectional"))
      (node (ref "CON2") (pin "P$4") (pinfunction "184_P$4") (pintype "bidirectional"))
      (node (ref "CON2") (pin "P$5") (pinfunction "185_P$5") (pintype "bidirectional"))
      (node (ref "CON2") (pin "P$6") (pinfunction "186_P$6") (pintype "bidirectional"))
      (node (ref "CON2") (pin "P$7") (pinfunction "187_P$7") (pintype "bidirectional"))
      (node (ref "CON2") (pin "P$8") (pinfunction "188_P$8") (pintype "bidirectional"))
      (node (ref "CON2") (pin "P$9") (pinfunction "189_P$9") (pintype "bidirectional"))
      (node (ref "CON4") (pin "4") (pinfunction "GND_4") (pintype "bidirectional"))
      (node (ref "CON5") (pin "4") (pinfunction "GND_4") (pintype "bidirectional"))
      (node (ref "CON6") (pin "4") (pinfunction "GND_4") (pintype "bidirectional"))
      (node (ref "CON7") (pin "4") (pinfunction "GND_4") (pintype "bidirectional"))
      (node (ref "CON8") (pin "4") (pinfunction "GND_4") (pintype "bidirectional"))
      (node (ref "LED2") (pin "C") (pinfunction "C_C") (pintype "passive"))
      (node (ref "LED4") (pin "C") (pinfunction "C_C") (pintype "passive"))
      (node (ref "LED5") (pin "C") (pinfunction "C_C") (pintype "passive"))
      (node (ref "PTH1") (pin "1") (pinfunction "1_1") (pintype "bidirectional"))
      (node (ref "PTH2") (pin "1") (pinfunction "1_1") (pintype "bidirectional"))
      (node (ref "PTH3") (pin "1") (pinfunction "1_1") (pintype "bidirectional"))
      (node (ref "PTH4") (pin "1") (pinfunction "1_1") (pintype "bidirectional"))
      (node (ref "PTH5") (pin "1") (pinfunction "1_1") (pintype "bidirectional"))
      (node (ref "PTH6") (pin "1") (pinfunction "1_1") (pintype "bidirectional"))
      (node (ref "PTH7") (pin "1") (pinfunction "1_1") (pintype "bidirectional"))
      (node (ref "PTH8") (pin "1") (pinfunction "1_1") (pintype "bidirectional"))
      (node (ref "U1") (pin "12") (pinfunction "GND_12") (pintype "bidirectional"))
      (node (ref "U10") (pin "12") (pinfunction "GND_12") (pintype "bidirectional"))
      (node (ref "U13") (pin "12") (pinfunction "GND_12") (pintype "bidirectional"))
      (node (ref "U13") (pin "20") (pinfunction "I11_20") (pintype "bidirectional"))
      (node (ref "U6") (pin "12") (pinfunction "GND_12") (pintype "bidirectional"))
      (node (ref "U8") (pin "12") (pinfunction "GND_12") (pintype "bidirectional"))
      (node (ref "U9") (pin "12") (pinfunction "GND_12") (pintype "bidirectional"))
    )
    (net (code "52") (name "IO0") (class "Default")
      (node (ref "CON2") (pin "6") (pinfunction "6_6") (pintype "bidirectional"))
      (node (ref "R3") (pin "1") (pinfunction "P$1_1") (pintype "passive"))
      (node (ref "U1") (pin "9") (pinfunction "I0_9") (pintype "bidirectional"))
    )
    (net (code "53") (name "IO1") (class "Default")
      (node (ref "CON2") (pin "5") (pinfunction "5_5") (pintype "bidirectional"))
      (node (ref "R7") (pin "1") (pinfunction "P$1_1") (pintype "passive"))
      (node (ref "U1") (pin "8") (pinfunction "I1_8") (pintype "bidirectional"))
    )
    (net (code "54") (name "IO2") (class "Default")
      (node (ref "CON2") (pin "8") (pinfunction "8_8") (pintype "bidirectional"))
      (node (ref "R8") (pin "1") (pinfunction "P$1_1") (pintype "passive"))
      (node (ref "U1") (pin "7") (pinfunction "I2_7") (pintype "bidirectional"))
    )
    (net (code "55") (name "IO3") (class "Default")
      (node (ref "CON2") (pin "7") (pinfunction "7_7") (pintype "bidirectional"))
      (node (ref "R9") (pin "1") (pinfunction "P$1_1") (pintype "passive"))
      (node (ref "U1") (pin "6") (pinfunction "I3_6") (pintype "bidirectional"))
    )
    (net (code "56") (name "IO4") (class "Default")
      (node (ref "CON2") (pin "10") (pinfunction "10_10") (pintype "bidirectional"))
      (node (ref "R10") (pin "1") (pinfunction "P$1_1") (pintype "passive"))
      (node (ref "U1") (pin "5") (pinfunction "I4_5") (pintype "bidirectional"))
    )
    (net (code "57") (name "IO5") (class "Default")
      (node (ref "CON2") (pin "9") (pinfunction "9_9") (pintype "bidirectional"))
      (node (ref "R11") (pin "1") (pinfunction "P$1_1") (pintype "passive"))
      (node (ref "U1") (pin "4") (pinfunction "I5_4") (pintype "bidirectional"))
    )
    (net (code "58") (name "IO6") (class "Default")
      (node (ref "CON2") (pin "12") (pinfunction "12_12") (pintype "bidirectional"))
      (node (ref "R12") (pin "1") (pinfunction "P$1_1") (pintype "passive"))
      (node (ref "U1") (pin "3") (pinfunction "I6_3") (pintype "bidirectional"))
    )
    (net (code "59") (name "IO7") (class "Default")
      (node (ref "CON2") (pin "11") (pinfunction "11_11") (pintype "bidirectional"))
      (node (ref "R13") (pin "1") (pinfunction "P$1_1") (pintype "passive"))
      (node (ref "U1") (pin "2") (pinfunction "I7_2") (pintype "bidirectional"))
    )
    (net (code "60") (name "IO8") (class "Default")
      (node (ref "CON2") (pin "14") (pinfunction "14_14") (pintype "bidirectional"))
      (node (ref "R14") (pin "1") (pinfunction "P$1_1") (pintype "passive"))
      (node (ref "U1") (pin "23") (pinfunction "I8_23") (pintype "bidirectional"))
    )
    (net (code "61") (name "IO9") (class "Default")
      (node (ref "CON2") (pin "13") (pinfunction "13_13") (pintype "bidirectional"))
      (node (ref "R15") (pin "1") (pinfunction "P$1_1") (pintype "passive"))
      (node (ref "U1") (pin "22") (pinfunction "I9_22") (pintype "bidirectional"))
    )
    (net (code "62") (name "IO10") (class "Default")
      (node (ref "CON2") (pin "16") (pinfunction "16_16") (pintype "bidirectional"))
      (node (ref "R16") (pin "1") (pinfunction "P$1_1") (pintype "passive"))
      (node (ref "U1") (pin "21") (pinfunction "I10_21") (pintype "bidirectional"))
    )
    (net (code "63") (name "IO11") (class "Default")
      (node (ref "CON2") (pin "15") (pinfunction "15_15") (pintype "bidirectional"))
      (node (ref "R17") (pin "1") (pinfunction "P$1_1") (pintype "passive"))
      (node (ref "U1") (pin "20") (pinfunction "I11_20") (pintype "bidirectional"))
    )
    (net (code "64") (name "IO12") (class "Default")
      (node (ref "CON2") (pin "18") (pinfunction "18_18") (pintype "bidirectional"))
      (node (ref "R18") (pin "1") (pinfunction "P$1_1") (pintype "passive"))
      (node (ref "U1") (pin "19") (pinfunction "I12_19") (pintype "bidirectional"))
    )
    (net (code "65") (name "IO13") (class "Default")
      (node (ref "CON2") (pin "17") (pinfunction "17_17") (pintype "bidirectional"))
      (node (ref "R19") (pin "1") (pinfunction "P$1_1") (pintype "passive"))
      (node (ref "U1") (pin "18") (pinfunction "I13_18") (pintype "bidirectional"))
    )
    (net (code "66") (name "IO14") (class "Default")
      (node (ref "CON2") (pin "20") (pinfunction "20_20") (pintype "bidirectional"))
      (node (ref "R21") (pin "1") (pinfunction "P$1_1") (pintype "passive"))
      (node (ref "U1") (pin "17") (pinfunction "I14_17") (pintype "bidirectional"))
    )
    (net (code "67") (name "IO15") (class "Default")
      (node (ref "CON2") (pin "19") (pinfunction "19_19") (pintype "bidirectional"))
      (node (ref "R22") (pin "1") (pinfunction "P$1_1") (pintype "passive"))
      (node (ref "U1") (pin "16") (pinfunction "I15_16") (pintype "bidirectional"))
    )
    (net (code "68") (name "IO16") (class "Default")
      (node (ref "CON2") (pin "22") (pinfunction "22_22") (pintype "bidirectional"))
      (node (ref "R28") (pin "2") (pinfunction "P$2_2") (pintype "passive"))
      (node (ref "U6") (pin "9") (pinfunction "I0_9") (pintype "bidirectional"))
    )
    (net (code "69") (name "IO17") (class "Default")
      (node (ref "CON2") (pin "21") (pinfunction "21_21") (pintype "bidirectional"))
      (node (ref "R27") (pin "2") (pinfunction "P$2_2") (pintype "passive"))
      (node (ref "U6") (pin "8") (pinfunction "I1_8") (pintype "bidirectional"))
    )
    (net (code "70") (name "IO18") (class "Default")
      (node (ref "CON2") (pin "24") (pinfunction "24_24") (pintype "bidirectional"))
      (node (ref "R26") (pin "2") (pinfunction "P$2_2") (pintype "passive"))
      (node (ref "U6") (pin "7") (pinfunction "I2_7") (pintype "bidirectional"))
    )
    (net (code "71") (name "IO19") (class "Default")
      (node (ref "CON2") (pin "23") (pinfunction "23_23") (pintype "bidirectional"))
      (node (ref "R25") (pin "2") (pinfunction "P$2_2") (pintype "passive"))
      (node (ref "U6") (pin "6") (pinfunction "I3_6") (pintype "bidirectional"))
    )
    (net (code "72") (name "IO20") (class "Default")
      (node (ref "CON2") (pin "26") (pinfunction "26_26") (pintype "bidirectional"))
      (node (ref "R24") (pin "2") (pinfunction "P$2_2") (pintype "passive"))
      (node (ref "U6") (pin "5") (pinfunction "I4_5") (pintype "bidirectional"))
    )
    (net (code "73") (name "IO21") (class "Default")
      (node (ref "CON2") (pin "25") (pinfunction "25_25") (pintype "bidirectional"))
      (node (ref "R23") (pin "2") (pinfunction "P$2_2") (pintype "passive"))
      (node (ref "U6") (pin "4") (pinfunction "I5_4") (pintype "bidirectional"))
    )
    (net (code "74") (name "IO22") (class "Default")
      (node (ref "U6") (pin "3") (pinfunction "I6_3") (pintype "bidirectional"))
    )
    (net (code "75") (name "IO23") (class "Default")
      (node (ref "U6") (pin "2") (pinfunction "I7_2") (pintype "bidirectional"))
    )
    (net (code "76") (name "IO24") (class "Default")
      (node (ref "U6") (pin "23") (pinfunction "I8_23") (pintype "bidirectional"))
    )
    (net (code "77") (name "IO25") (class "Default")
      (node (ref "U6") (pin "22") (pinfunction "I9_22") (pintype "bidirectional"))
    )
    (net (code "78") (name "IO26") (class "Default")
      (node (ref "U6") (pin "21") (pinfunction "I10_21") (pintype "bidirectional"))
    )
    (net (code "79") (name "IO27") (class "Default")
      (node (ref "U6") (pin "20") (pinfunction "I11_20") (pintype "bidirectional"))
    )
    (net (code "80") (name "IO28") (class "Default")
      (node (ref "U6") (pin "19") (pinfunction "I12_19") (pintype "bidirectional"))
    )
    (net (code "81") (name "IO29") (class "Default")
      (node (ref "U6") (pin "18") (pinfunction "I13_18") (pintype "bidirectional"))
    )
    (net (code "82") (name "IO30") (class "Default")
      (node (ref "U6") (pin "17") (pinfunction "I14_17") (pintype "bidirectional"))
    )
    (net (code "83") (name "IO31") (class "Default")
      (node (ref "U6") (pin "16") (pinfunction "I15_16") (pintype "bidirectional"))
    )
    (net (code "84") (name "IO48") (class "Default")
      (node (ref "U8") (pin "9") (pinfunction "I0_9") (pintype "bidirectional"))
    )
    (net (code "85") (name "IO49") (class "Default")
      (node (ref "U8") (pin "8") (pinfunction "I1_8") (pintype "bidirectional"))
    )
    (net (code "86") (name "IO50") (class "Default")
      (node (ref "U8") (pin "7") (pinfunction "I2_7") (pintype "bidirectional"))
    )
    (net (code "87") (name "IO51") (class "Default")
      (node (ref "R2") (pin "2") (pinfunction "P$2_2") (pintype "passive"))
      (node (ref "TP14") (pin "TP") (pinfunction "TP_TP") (pintype "input"))
      (node (ref "U8") (pin "6") (pinfunction "I3_6") (pintype "bidirectional"))
    )
    (net (code "88") (name "IO52") (class "Default")
      (node (ref "CON1") (pin "1") (pinfunction "A/D0_1") (pintype "bidirectional"))
      (node (ref "CON2") (pin "58") (pinfunction "58_58") (pintype "bidirectional"))
      (node (ref "U8") (pin "5") (pinfunction "I4_5") (pintype "bidirectional"))
    )
    (net (code "89") (name "IO53") (class "Default")
      (node (ref "CON1") (pin "2") (pinfunction "A/D1_2") (pintype "bidirectional"))
      (node (ref "CON2") (pin "57") (pinfunction "57_57") (pintype "bidirectional"))
      (node (ref "U8") (pin "4") (pinfunction "I5_4") (pintype "bidirectional"))
    )
    (net (code "90") (name "IO54") (class "Default")
      (node (ref "CON2") (pin "60") (pinfunction "60_60") (pintype "bidirectional"))
      (node (ref "CON4") (pin "1") (pinfunction "A/D0_1") (pintype "bidirectional"))
      (node (ref "U8") (pin "3") (pinfunction "I6_3") (pintype "bidirectional"))
    )
    (net (code "91") (name "IO55") (class "Default")
      (node (ref "CON2") (pin "59") (pinfunction "59_59") (pintype "bidirectional"))
      (node (ref "CON4") (pin "2") (pinfunction "A/D1_2") (pintype "bidirectional"))
      (node (ref "U8") (pin "2") (pinfunction "I7_2") (pintype "bidirectional"))
    )
    (net (code "92") (name "IO56") (class "Default")
      (node (ref "CON2") (pin "62") (pinfunction "62_62") (pintype "bidirectional"))
      (node (ref "CON5") (pin "1") (pinfunction "A/D0_1") (pintype "bidirectional"))
      (node (ref "U8") (pin "23") (pinfunction "I8_23") (pintype "bidirectional"))
    )
    (net (code "93") (name "IO57") (class "Default")
      (node (ref "CON2") (pin "61") (pinfunction "61_61") (pintype "bidirectional"))
      (node (ref "CON5") (pin "2") (pinfunction "A/D1_2") (pintype "bidirectional"))
      (node (ref "U8") (pin "22") (pinfunction "I9_22") (pintype "bidirectional"))
    )
    (net (code "94") (name "IO58") (class "Default")
      (node (ref "CON2") (pin "64") (pinfunction "64_64") (pintype "bidirectional"))
      (node (ref "CON6") (pin "1") (pinfunction "A/D0_1") (pintype "bidirectional"))
      (node (ref "U8") (pin "21") (pinfunction "I10_21") (pintype "bidirectional"))
    )
    (net (code "95") (name "IO59") (class "Default")
      (node (ref "CON2") (pin "63") (pinfunction "63_63") (pintype "bidirectional"))
      (node (ref "CON6") (pin "2") (pinfunction "A/D1_2") (pintype "bidirectional"))
      (node (ref "U8") (pin "20") (pinfunction "I11_20") (pintype "bidirectional"))
    )
    (net (code "96") (name "IO60") (class "Default")
      (node (ref "CON2") (pin "66") (pinfunction "66_66") (pintype "bidirectional"))
      (node (ref "CON7") (pin "1") (pinfunction "A/D0_1") (pintype "bidirectional"))
      (node (ref "U8") (pin "19") (pinfunction "I12_19") (pintype "bidirectional"))
    )
    (net (code "97") (name "IO61") (class "Default")
      (node (ref "CON2") (pin "65") (pinfunction "65_65") (pintype "bidirectional"))
      (node (ref "CON7") (pin "2") (pinfunction "A/D1_2") (pintype "bidirectional"))
      (node (ref "U8") (pin "18") (pinfunction "I13_18") (pintype "bidirectional"))
    )
    (net (code "98") (name "IO62") (class "Default")
      (node (ref "CON2") (pin "68") (pinfunction "68_68") (pintype "bidirectional"))
      (node (ref "CON8") (pin "1") (pinfunction "A/D0_1") (pintype "bidirectional"))
      (node (ref "U8") (pin "17") (pinfunction "I14_17") (pintype "bidirectional"))
    )
    (net (code "99") (name "IO63") (class "Default")
      (node (ref "CON2") (pin "67") (pinfunction "67_67") (pintype "bidirectional"))
      (node (ref "CON8") (pin "2") (pinfunction "A/D1_2") (pintype "bidirectional"))
      (node (ref "U8") (pin "16") (pinfunction "I15_16") (pintype "bidirectional"))
    )
    (net (code "100") (name "IO64") (class "Default")
      (node (ref "CON12") (pin "1") (pinfunction "A/D0_1") (pintype "bidirectional"))
      (node (ref "CON2") (pin "70") (pinfunction "70_70") (pintype "bidirectional"))
      (node (ref "U9") (pin "9") (pinfunction "I0_9") (pintype "bidirectional"))
    )
    (net (code "101") (name "IO65") (class "Default")
      (node (ref "CON12") (pin "2") (pinfunction "A/D1_2") (pintype "bidirectional"))
      (node (ref "CON2") (pin "69") (pinfunction "69_69") (pintype "bidirectional"))
      (node (ref "U9") (pin "8") (pinfunction "I1_8") (pintype "bidirectional"))
    )
    (net (code "102") (name "IO66") (class "Default")
      (node (ref "CON13") (pin "1") (pinfunction "A/D0_1") (pintype "bidirectional"))
      (node (ref "CON2") (pin "72") (pinfunction "72_72") (pintype "bidirectional"))
      (node (ref "U9") (pin "7") (pinfunction "I2_7") (pintype "bidirectional"))
    )
    (net (code "103") (name "IO67") (class "Default")
      (node (ref "CON13") (pin "2") (pinfunction "A/D1_2") (pintype "bidirectional"))
      (node (ref "CON2") (pin "71") (pinfunction "71_71") (pintype "bidirectional"))
      (node (ref "U9") (pin "6") (pinfunction "I3_6") (pintype "bidirectional"))
    )
    (net (code "104") (name "IO68") (class "Default")
      (node (ref "U9") (pin "5") (pinfunction "I4_5") (pintype "bidirectional"))
    )
    (net (code "105") (name "IO69") (class "Default")
      (node (ref "U9") (pin "4") (pinfunction "I5_4") (pintype "bidirectional"))
    )
    (net (code "106") (name "IO70") (class "Default")
      (node (ref "U9") (pin "3") (pinfunction "I6_3") (pintype "bidirectional"))
    )
    (net (code "107") (name "IO71") (class "Default")
      (node (ref "U9") (pin "2") (pinfunction "I7_2") (pintype "bidirectional"))
    )
    (net (code "108") (name "IO72") (class "Default")
      (node (ref "U9") (pin "23") (pinfunction "I8_23") (pintype "bidirectional"))
    )
    (net (code "109") (name "IO73") (class "Default")
      (node (ref "U9") (pin "22") (pinfunction "I9_22") (pintype "bidirectional"))
    )
    (net (code "110") (name "IO74") (class "Default")
      (node (ref "U9") (pin "21") (pinfunction "I10_21") (pintype "bidirectional"))
    )
    (net (code "111") (name "IO75") (class "Default")
      (node (ref "U9") (pin "20") (pinfunction "I11_20") (pintype "bidirectional"))
    )
    (net (code "112") (name "IO76") (class "Default")
      (node (ref "U9") (pin "19") (pinfunction "I12_19") (pintype "bidirectional"))
    )
    (net (code "113") (name "IO77") (class "Default")
      (node (ref "U9") (pin "18") (pinfunction "I13_18") (pintype "bidirectional"))
    )
    (net (code "114") (name "IO78") (class "Default")
      (node (ref "U9") (pin "17") (pinfunction "I14_17") (pintype "bidirectional"))
    )
    (net (code "115") (name "IO79") (class "Default")
      (node (ref "U9") (pin "16") (pinfunction "I15_16") (pintype "bidirectional"))
    )
    (net (code "116") (name "IO80") (class "Default")
      (node (ref "U10") (pin "9") (pinfunction "I0_9") (pintype "bidirectional"))
    )
    (net (code "117") (name "IO81") (class "Default")
      (node (ref "U10") (pin "8") (pinfunction "I1_8") (pintype "bidirectional"))
    )
    (net (code "118") (name "IO82") (class "Default")
      (node (ref "U10") (pin "7") (pinfunction "I2_7") (pintype "bidirectional"))
    )
    (net (code "119") (name "IO83") (class "Default")
      (node (ref "U10") (pin "6") (pinfunction "I3_6") (pintype "bidirectional"))
    )
    (net (code "120") (name "IO84") (class "Default")
      (node (ref "U10") (pin "5") (pinfunction "I4_5") (pintype "bidirectional"))
    )
    (net (code "121") (name "IO85") (class "Default")
      (node (ref "U10") (pin "4") (pinfunction "I5_4") (pintype "bidirectional"))
    )
    (net (code "122") (name "IO86") (class "Default")
      (node (ref "U10") (pin "3") (pinfunction "I6_3") (pintype "bidirectional"))
    )
    (net (code "123") (name "IO87") (class "Default")
      (node (ref "U10") (pin "2") (pinfunction "I7_2") (pintype "bidirectional"))
    )
    (net (code "124") (name "IO88") (class "Default")
      (node (ref "U10") (pin "23") (pinfunction "I8_23") (pintype "bidirectional"))
    )
    (net (code "125") (name "IO89") (class "Default")
      (node (ref "U10") (pin "22") (pinfunction "I9_22") (pintype "bidirectional"))
    )
    (net (code "126") (name "IO90") (class "Default")
      (node (ref "U10") (pin "21") (pinfunction "I10_21") (pintype "bidirectional"))
    )
    (net (code "127") (name "IO91") (class "Default")
      (node (ref "U10") (pin "20") (pinfunction "I11_20") (pintype "bidirectional"))
    )
    (net (code "128") (name "IO92") (class "Default")
      (node (ref "U10") (pin "19") (pinfunction "I12_19") (pintype "bidirectional"))
    )
    (net (code "129") (name "IO93") (class "Default")
      (node (ref "U10") (pin "18") (pinfunction "I13_18") (pintype "bidirectional"))
    )
    (net (code "130") (name "IO94") (class "Default")
      (node (ref "U10") (pin "17") (pinfunction "I14_17") (pintype "bidirectional"))
    )
    (net (code "131") (name "IO95") (class "Default")
      (node (ref "U10") (pin "16") (pinfunction "I15_16") (pintype "bidirectional"))
    )
    (net (code "132") (name "IOREF") (class "Default")
      (node (ref "BRD1") (pin "2") (pinfunction "IOREF_2") (pintype "bidirectional"))
      (node (ref "TP13") (pin "TP") (pinfunction "TP_TP") (pintype "input"))
    )
    (net (code "133") (name "MUX_EN") (class "Default")
      (node (ref "CON2") (pin "169") (pinfunction "169_169") (pintype "bidirectional"))
      (node (ref "R1") (pin "1") (pinfunction "P$1_1") (pintype "passive"))
      (node (ref "R4") (pin "1") (pinfunction "P$1_1") (pintype "passive"))
      (node (ref "R45") (pin "1") (pinfunction "P$1_1") (pintype "passive"))
      (node (ref "R46") (pin "1") (pinfunction "P$1_1") (pintype "passive"))
      (node (ref "R52") (pin "1") (pinfunction "P$1_1") (pintype "passive"))
      (node (ref "R6") (pin "1") (pinfunction "P$1_1") (pintype "passive"))
    )
    (net (code "134") (name "NRESET") (class "Default")
      (node (ref "BRD1") (pin "3") (pinfunction "NRESET_3") (pintype "bidirectional"))
      (node (ref "R2") (pin "1") (pinfunction "P$1_1") (pintype "passive"))
      (node (ref "TP4") (pin "TP") (pinfunction "TP_TP") (pintype "input"))
    )
    (net (code "135") (name "Net-(R1-P$2)") (class "Default")
      (node (ref "R1") (pin "2") (pinfunction "P$2_2") (pintype "passive"))
      (node (ref "U1") (pin "15") (pinfunction "\\E_15") (pintype "bidirectional"))
    )
    (net (code "136") (name "Net-(R4-P$2)") (class "Default")
      (node (ref "R4") (pin "2") (pinfunction "P$2_2") (pintype "passive"))
      (node (ref "U6") (pin "15") (pinfunction "\\E_15") (pintype "bidirectional"))
    )
    (net (code "137") (name "Net-(R6-P$2)") (class "Default")
      (node (ref "R6") (pin "2") (pinfunction "P$2_2") (pintype "passive"))
      (node (ref "U8") (pin "15") (pinfunction "\\E_15") (pintype "bidirectional"))
    )
    (net (code "138") (name "Net-(R44-P$1)") (class "Default")
      (node (ref "LED2") (pin "A") (pinfunction "A_A") (pintype "passive"))
      (node (ref "R44") (pin "1") (pinfunction "P$1_1") (pintype "passive"))
    )
    (net (code "139") (name "Net-(R45-P$2)") (class "Default")
      (node (ref "R45") (pin "2") (pinfunction "P$2_2") (pintype "passive"))
      (node (ref "U9") (pin "15") (pinfunction "\\E_15") (pintype "bidirectional"))
    )
    (net (code "140") (name "Net-(R46-P$2)") (class "Default")
      (node (ref "R46") (pin "2") (pinfunction "P$2_2") (pintype "passive"))
      (node (ref "U10") (pin "15") (pinfunction "\\E_15") (pintype "bidirectional"))
    )
    (net (code "141") (name "Net-(R49-P$1)") (class "Default")
      (node (ref "LED4") (pin "A") (pinfunction "A_A") (pintype "passive"))
      (node (ref "R49") (pin "1") (pinfunction "P$1_1") (pintype "passive"))
    )
    (net (code "142") (name "Net-(R50-P$1)") (class "Default")
      (node (ref "LED5") (pin "A") (pinfunction "A_A") (pintype "passive"))
      (node (ref "R50") (pin "1") (pinfunction "P$1_1") (pintype "passive"))
    )
    (net (code "143") (name "Net-(R52-P$2)") (class "Default")
      (node (ref "R52") (pin "2") (pinfunction "P$2_2") (pintype "passive"))
      (node (ref "U13") (pin "15") (pinfunction "\\E_15") (pintype "bidirectional"))
    )
    (net (code "144") (name "Net-(U13-I12)") (class "Default")
      (node (ref "TP1") (pin "TP") (pinfunction "TP_TP") (pintype "input"))
      (node (ref "U13") (pin "19") (pinfunction "I12_19") (pintype "bidirectional"))
    )
    (net (code "145") (name "Net-(U13-I13)") (class "Default")
      (node (ref "TP15") (pin "TP") (pinfunction "TP_TP") (pintype "input"))
      (node (ref "U13") (pin "18") (pinfunction "I13_18") (pintype "bidirectional"))
    )
    (net (code "146") (name "Net-(U13-I14)") (class "Default")
      (node (ref "TP16") (pin "TP") (pinfunction "TP_TP") (pintype "input"))
      (node (ref "U13") (pin "17") (pinfunction "I14_17") (pintype "bidirectional"))
    )
    (net (code "147") (name "Net-(U13-I15)") (class "Default")
      (node (ref "TP17") (pin "TP") (pinfunction "TP_TP") (pintype "input"))
      (node (ref "U13") (pin "16") (pinfunction "I15_16") (pintype "bidirectional"))
    )
    (net (code "148") (name "VDDIO") (class "Default")
      (node (ref "C21") (pin "1") (pinfunction "P$1_1") (pintype "passive"))
      (node (ref "C22") (pin "1") (pinfunction "P$1_1") (pintype "passive"))
      (node (ref "CON2") (pin "1") (pinfunction "1_1") (pintype "bidirectional"))
      (node (ref "CON2") (pin "2") (pinfunction "2_2") (pintype "bidirectional"))
      (node (ref "CON2") (pin "3") (pinfunction "3_3") (pintype "bidirectional"))
      (node (ref "CON2") (pin "4") (pinfunction "4_4") (pintype "bidirectional"))
      (node (ref "R50") (pin "2") (pinfunction "P$2_2") (pintype "passive"))
      (node (ref "TP6") (pin "TP") (pinfunction "TP_TP") (pintype "input"))
      (node (ref "U13") (pin "21") (pinfunction "I10_21") (pintype "bidirectional"))
    )
    (net (code "149") (name "VIN_DUT") (class "Default")
      (node (ref "BRD1") (pin "8") (pinfunction "VIN_8") (pintype "bidirectional"))
      (node (ref "TP11") (pin "TP") (pinfunction "TP_TP") (pintype "input"))
    )
    (net (code "150") (name "unconnected-(BRD1-NC-Pad1)") (class "Default")
      (node (ref "BRD1") (pin "1") (pinfunction "NC_1") (pintype "bidirectional"))
    )
    (net (code "151") (name "unconnected-(CON2-Pad27)") (class "Default")
      (node (ref "CON2") (pin "27") (pinfunction "27_27") (pintype "bidirectional"))
    )
    (net (code "152") (name "unconnected-(CON2-Pad28)") (class "Default")
      (node (ref "CON2") (pin "28") (pinfunction "28_28") (pintype "bidirectional"))
    )
    (net (code "153") (name "unconnected-(CON2-Pad29)") (class "Default")
      (node (ref "CON2") (pin "29") (pinfunction "29_29") (pintype "bidirectional"))
    )
    (net (code "154") (name "unconnected-(CON2-Pad30)") (class "Default")
      (node (ref "CON2") (pin "30") (pinfunction "30_30") (pintype "bidirectional"))
    )
    (net (code "155") (name "unconnected-(CON2-Pad31)") (class "Default")
      (node (ref "CON2") (pin "31") (pinfunction "31_31") (pintype "bidirectional"))
    )
    (net (code "156") (name "unconnected-(CON2-Pad32)") (class "Default")
      (node (ref "CON2") (pin "32") (pinfunction "32_32") (pintype "bidirectional"))
    )
    (net (code "157") (name "unconnected-(CON2-Pad33)") (class "Default")
      (node (ref "CON2") (pin "33") (pinfunction "33_33") (pintype "bidirectional"))
    )
    (net (code "158") (name "unconnected-(CON2-Pad34)") (class "Default")
      (node (ref "CON2") (pin "34") (pinfunction "34_34") (pintype "bidirectional"))
    )
    (net (code "159") (name "unconnected-(CON2-Pad35)") (class "Default")
      (node (ref "CON2") (pin "35") (pinfunction "35_35") (pintype "bidirectional"))
    )
    (net (code "160") (name "unconnected-(CON2-Pad36)") (class "Default")
      (node (ref "CON2") (pin "36") (pinfunction "36_36") (pintype "bidirectional"))
    )
    (net (code "161") (name "unconnected-(CON2-Pad37)") (class "Default")
      (node (ref "CON2") (pin "37") (pinfunction "37_37") (pintype "bidirectional"))
    )
    (net (code "162") (name "unconnected-(CON2-Pad38)") (class "Default")
      (node (ref "CON2") (pin "38") (pinfunction "38_38") (pintype "bidirectional"))
    )
    (net (code "163") (name "unconnected-(CON2-Pad39)") (class "Default")
      (node (ref "CON2") (pin "39") (pinfunction "39_39") (pintype "bidirectional"))
    )
    (net (code "164") (name "unconnected-(CON2-Pad40)") (class "Default")
      (node (ref "CON2") (pin "40") (pinfunction "40_40") (pintype "bidirectional"))
    )
    (net (code "165") (name "unconnected-(CON2-Pad41)") (class "Default")
      (node (ref "CON2") (pin "41") (pinfunction "41_41") (pintype "bidirectional"))
    )
    (net (code "166") (name "unconnected-(CON2-Pad42)") (class "Default")
      (node (ref "CON2") (pin "42") (pinfunction "42_42") (pintype "bidirectional"))
    )
    (net (code "167") (name "unconnected-(CON2-Pad43)") (class "Default")
      (node (ref "CON2") (pin "43") (pinfunction "43_43") (pintype "bidirectional"))
    )
    (net (code "168") (name "unconnected-(CON2-Pad44)") (class "Default")
      (node (ref "CON2") (pin "44") (pinfunction "44_44") (pintype "bidirectional"))
    )
    (net (code "169") (name "unconnected-(CON2-Pad45)") (class "Default")
      (node (ref "CON2") (pin "45") (pinfunction "45_45") (pintype "bidirectional"))
    )
    (net (code "170") (name "unconnected-(CON2-Pad46)") (class "Default")
      (node (ref "CON2") (pin "46") (pinfunction "46_46") (pintype "bidirectional"))
    )
    (net (code "171") (name "unconnected-(CON2-Pad47)") (class "Default")
      (node (ref "CON2") (pin "47") (pinfunction "47_47") (pintype "bidirectional"))
    )
    (net (code "172") (name "unconnected-(CON2-Pad48)") (class "Default")
      (node (ref "CON2") (pin "48") (pinfunction "48_48") (pintype "bidirectional"))
    )
    (net (code "173") (name "unconnected-(CON2-Pad49)") (class "Default")
      (node (ref "CON2") (pin "49") (pinfunction "49_49") (pintype "bidirectional"))
    )
    (net (code "174") (name "unconnected-(CON2-Pad50)") (class "Default")
      (node (ref "CON2") (pin "50") (pinfunction "50_50") (pintype "bidirectional"))
    )
    (net (code "175") (name "unconnected-(CON2-Pad51)") (class "Default")
      (node (ref "CON2") (pin "51") (pinfunction "51_51") (pintype "bidirectional"))
    )
    (net (code "176") (name "unconnected-(CON2-Pad52)") (class "Default")
      (node (ref "CON2") (pin "52") (pinfunction "52_52") (pintype "bidirectional"))
    )
    (net (code "177") (name "unconnected-(CON2-Pad53)") (class "Default")
      (node (ref "CON2") (pin "53") (pinfunction "53_53") (pintype "bidirectional"))
    )
    (net (code "178") (name "unconnected-(CON2-Pad54)") (class "Default")
      (node (ref "CON2") (pin "54") (pinfunction "54_54") (pintype "bidirectional"))
    )
    (net (code "179") (name "unconnected-(CON2-Pad55)") (class "Default")
      (node (ref "CON2") (pin "55") (pinfunction "55_55") (pintype "bidirectional"))
    )
    (net (code "180") (name "unconnected-(CON2-Pad56)") (class "Default")
      (node (ref "CON2") (pin "56") (pinfunction "56_56") (pintype "bidirectional"))
    )
    (net (code "181") (name "unconnected-(CON2-Pad73)") (class "Default")
      (node (ref "CON2") (pin "73") (pinfunction "73_73") (pintype "bidirectional"))
    )
    (net (code "182") (name "unconnected-(CON2-Pad74)") (class "Default")
      (node (ref "CON2") (pin "74") (pinfunction "74_74") (pintype "bidirectional"))
    )
    (net (code "183") (name "unconnected-(CON2-Pad75)") (class "Default")
      (node (ref "CON2") (pin "75") (pinfunction "75_75") (pintype "bidirectional"))
    )
    (net (code "184") (name "unconnected-(CON2-Pad76)") (class "Default")
      (node (ref "CON2") (pin "76") (pinfunction "76_76") (pintype "bidirectional"))
    )
    (net (code "185") (name "unconnected-(CON2-Pad77)") (class "Default")
      (node (ref "CON2") (pin "77") (pinfunction "77_77") (pintype "bidirectional"))
    )
    (net (code "186") (name "unconnected-(CON2-Pad78)") (class "Default")
      (node (ref "CON2") (pin "78") (pinfunction "78_78") (pintype "bidirectional"))
    )
    (net (code "187") (name "unconnected-(CON2-Pad79)") (class "Default")
      (node (ref "CON2") (pin "79") (pinfunction "79_79") (pintype "bidirectional"))
    )
    (net (code "188") (name "unconnected-(CON2-Pad80)") (class "Default")
      (node (ref "CON2") (pin "80") (pinfunction "80_80") (pintype "bidirectional"))
    )
    (net (code "189") (name "unconnected-(CON2-Pad81)") (class "Default")
      (node (ref "CON2") (pin "81") (pinfunction "81_81") (pintype "bidirectional"))
    )
    (net (code "190") (name "unconnected-(CON2-Pad82)") (class "Default")
      (node (ref "CON2") (pin "82") (pinfunction "82_82") (pintype "bidirectional"))
    )
    (net (code "191") (name "unconnected-(CON2-Pad83)") (class "Default")
      (node (ref "CON2") (pin "83") (pinfunction "83_83") (pintype "bidirectional"))
    )
    (net (code "192") (name "unconnected-(CON2-Pad84)") (class "Default")
      (node (ref "CON2") (pin "84") (pinfunction "84_84") (pintype "bidirectional"))
    )
    (net (code "193") (name "unconnected-(CON2-Pad85)") (class "Default")
      (node (ref "CON2") (pin "85") (pinfunction "85_85") (pintype "bidirectional"))
    )
    (net (code "194") (name "unconnected-(CON2-Pad86)") (class "Default")
      (node (ref "CON2") (pin "86") (pinfunction "86_86") (pintype "bidirectional"))
    )
    (net (code "195") (name "unconnected-(CON2-Pad87)") (class "Default")
      (node (ref "CON2") (pin "87") (pinfunction "87_87") (pintype "bidirectional"))
    )
    (net (code "196") (name "unconnected-(CON2-Pad88)") (class "Default")
      (node (ref "CON2") (pin "88") (pinfunction "88_88") (pintype "bidirectional"))
    )
    (net (code "197") (name "unconnected-(CON2-Pad89)") (class "Default")
      (node (ref "CON2") (pin "89") (pinfunction "89_89") (pintype "bidirectional"))
    )
    (net (code "198") (name "unconnected-(CON2-Pad90)") (class "Default")
      (node (ref "CON2") (pin "90") (pinfunction "90_90") (pintype "bidirectional"))
    )
    (net (code "199") (name "unconnected-(CON2-Pad91)") (class "Default")
      (node (ref "CON2") (pin "91") (pinfunction "91_91") (pintype "bidirectional"))
    )
    (net (code "200") (name "unconnected-(CON2-Pad92)") (class "Default")
      (node (ref "CON2") (pin "92") (pinfunction "92_92") (pintype "bidirectional"))
    )
    (net (code "201") (name "unconnected-(CON2-Pad93)") (class "Default")
      (node (ref "CON2") (pin "93") (pinfunction "93_93") (pintype "bidirectional"))
    )
    (net (code "202") (name "unconnected-(CON2-Pad94)") (class "Default")
      (node (ref "CON2") (pin "94") (pinfunction "94_94") (pintype "bidirectional"))
    )
    (net (code "203") (name "unconnected-(CON2-Pad95)") (class "Default")
      (node (ref "CON2") (pin "95") (pinfunction "95_95") (pintype "bidirectional"))
    )
    (net (code "204") (name "unconnected-(CON2-Pad96)") (class "Default")
      (node (ref "CON2") (pin "96") (pinfunction "96_96") (pintype "bidirectional"))
    )
    (net (code "205") (name "unconnected-(CON2-Pad97)") (class "Default")
      (node (ref "CON2") (pin "97") (pinfunction "97_97") (pintype "bidirectional"))
    )
    (net (code "206") (name "unconnected-(CON2-Pad98)") (class "Default")
      (node (ref "CON2") (pin "98") (pinfunction "98_98") (pintype "bidirectional"))
    )
    (net (code "207") (name "unconnected-(CON2-Pad99)") (class "Default")
      (node (ref "CON2") (pin "99") (pinfunction "99_99") (pintype "bidirectional"))
    )
    (net (code "208") (name "unconnected-(CON2-Pad100)") (class "Default")
      (node (ref "CON2") (pin "100") (pinfunction "100_100") (pintype "bidirectional"))
    )
    (net (code "209") (name "unconnected-(CON2-Pad101)") (class "Default")
      (node (ref "CON2") (pin "101") (pinfunction "101_101") (pintype "bidirectional"))
    )
    (net (code "210") (name "unconnected-(CON2-Pad102)") (class "Default")
      (node (ref "CON2") (pin "102") (pinfunction "102_102") (pintype "bidirectional"))
    )
    (net (code "211") (name "unconnected-(CON2-Pad103)") (class "Default")
      (node (ref "CON2") (pin "103") (pinfunction "103_103") (pintype "bidirectional"))
    )
    (net (code "212") (name "unconnected-(CON2-Pad104)") (class "Default")
      (node (ref "CON2") (pin "104") (pinfunction "104_104") (pintype "bidirectional"))
    )
    (net (code "213") (name "unconnected-(CON2-Pad105)") (class "Default")
      (node (ref "CON2") (pin "105") (pinfunction "105_105") (pintype "bidirectional"))
    )
    (net (code "214") (name "unconnected-(CON2-Pad106)") (class "Default")
      (node (ref "CON2") (pin "106") (pinfunction "106_106") (pintype "bidirectional"))
    )
    (net (code "215") (name "unconnected-(CON2-Pad107)") (class "Default")
      (node (ref "CON2") (pin "107") (pinfunction "107_107") (pintype "bidirectional"))
    )
    (net (code "216") (name "unconnected-(CON2-Pad108)") (class "Default")
      (node (ref "CON2") (pin "108") (pinfunction "108_108") (pintype "bidirectional"))
    )
    (net (code "217") (name "unconnected-(CON2-Pad109)") (class "Default")
      (node (ref "CON2") (pin "109") (pinfunction "109_109") (pintype "bidirectional"))
    )
    (net (code "218") (name "unconnected-(CON2-Pad110)") (class "Default")
      (node (ref "CON2") (pin "110") (pinfunction "110_110") (pintype "bidirectional"))
    )
    (net (code "219") (name "unconnected-(CON2-Pad111)") (class "Default")
      (node (ref "CON2") (pin "111") (pinfunction "111_111") (pintype "bidirectional"))
    )
    (net (code "220") (name "unconnected-(CON2-Pad112)") (class "Default")
      (node (ref "CON2") (pin "112") (pinfunction "112_112") (pintype "bidirectional"))
    )
    (net (code "221") (name "unconnected-(CON2-Pad113)") (class "Default")
      (node (ref "CON2") (pin "113") (pinfunction "113_113") (pintype "bidirectional"))
    )
    (net (code "222") (name "unconnected-(CON2-Pad114)") (class "Default")
      (node (ref "CON2") (pin "114") (pinfunction "114_114") (pintype "bidirectional"))
    )
    (net (code "223") (name "unconnected-(CON2-Pad115)") (class "Default")
      (node (ref "CON2") (pin "115") (pinfunction "115_115") (pintype "bidirectional"))
    )
    (net (code "224") (name "unconnected-(CON2-Pad116)") (class "Default")
      (node (ref "CON2") (pin "116") (pinfunction "116_116") (pintype "bidirectional"))
    )
    (net (code "225") (name "unconnected-(CON2-Pad117)") (class "Default")
      (node (ref "CON2") (pin "117") (pinfunction "117_117") (pintype "bidirectional"))
    )
    (net (code "226") (name "unconnected-(CON2-Pad118)") (class "Default")
      (node (ref "CON2") (pin "118") (pinfunction "118_118") (pintype "bidirectional"))
    )
    (net (code "227") (name "unconnected-(CON2-Pad119)") (class "Default")
      (node (ref "CON2") (pin "119") (pinfunction "119_119") (pintype "bidirectional"))
    )
    (net (code "228") (name "unconnected-(CON2-Pad120)") (class "Default")
      (node (ref "CON2") (pin "120") (pinfunction "120_120") (pintype "bidirectional"))
    )
    (net (code "229") (name "unconnected-(CON2-Pad121)") (class "Default")
      (node (ref "CON2") (pin "121") (pinfunction "121_121") (pintype "bidirectional"))
    )
    (net (code "230") (name "unconnected-(CON2-Pad122)") (class "Default")
      (node (ref "CON2") (pin "122") (pinfunction "122_122") (pintype "bidirectional"))
    )
    (net (code "231") (name "unconnected-(CON2-Pad123)") (class "Default")
      (node (ref "CON2") (pin "123") (pinfunction "123_123") (pintype "bidirectional"))
    )
    (net (code "232") (name "unconnected-(CON2-Pad124)") (class "Default")
      (node (ref "CON2") (pin "124") (pinfunction "124_124") (pintype "bidirectional"))
    )
    (net (code "233") (name "unconnected-(CON2-Pad125)") (class "Default")
      (node (ref "CON2") (pin "125") (pinfunction "125_125") (pintype "bidirectional"))
    )
    (net (code "234") (name "unconnected-(CON2-Pad126)") (class "Default")
      (node (ref "CON2") (pin "126") (pinfunction "126_126") (pintype "bidirectional"))
    )
    (net (code "235") (name "unconnected-(CON2-Pad127)") (class "Default")
      (node (ref "CON2") (pin "127") (pinfunction "127_127") (pintype "bidirectional"))
    )
    (net (code "236") (name "unconnected-(CON2-Pad128)") (class "Default")
      (node (ref "CON2") (pin "128") (pinfunction "128_128") (pintype "bidirectional"))
    )
    (net (code "237") (name "unconnected-(CON2-Pad129)") (class "Default")
      (node (ref "CON2") (pin "129") (pinfunction "129_129") (pintype "bidirectional"))
    )
    (net (code "238") (name "unconnected-(CON2-Pad130)") (class "Default")
      (node (ref "CON2") (pin "130") (pinfunction "130_130") (pintype "bidirectional"))
    )
    (net (code "239") (name "unconnected-(CON2-Pad131)") (class "Default")
      (node (ref "CON2") (pin "131") (pinfunction "131_131") (pintype "bidirectional"))
    )
    (net (code "240") (name "unconnected-(CON2-Pad132)") (class "Default")
      (node (ref "CON2") (pin "132") (pinfunction "132_132") (pintype "bidirectional"))
    )
    (net (code "241") (name "unconnected-(CON2-Pad137)") (class "Default")
      (node (ref "CON2") (pin "137") (pinfunction "137_137") (pintype "bidirectional"))
    )
    (net (code "242") (name "unconnected-(CON2-Pad138)") (class "Default")
      (node (ref "CON2") (pin "138") (pinfunction "138_138") (pintype "bidirectional"))
    )
    (net (code "243") (name "unconnected-(CON2-Pad139)") (class "Default")
      (node (ref "CON2") (pin "139") (pinfunction "139_139") (pintype "bidirectional"))
    )
    (net (code "244") (name "unconnected-(CON2-Pad140)") (class "Default")
      (node (ref "CON2") (pin "140") (pinfunction "140_140") (pintype "bidirectional"))
    )
    (net (code "245") (name "unconnected-(CON2-Pad141)") (class "Default")
      (node (ref "CON2") (pin "141") (pinfunction "141_141") (pintype "bidirectional"))
    )
    (net (code "246") (name "unconnected-(CON2-Pad142)") (class "Default")
      (node (ref "CON2") (pin "142") (pinfunction "142_142") (pintype "bidirectional"))
    )
    (net (code "247") (name "unconnected-(CON2-Pad143)") (class "Default")
      (node (ref "CON2") (pin "143") (pinfunction "143_143") (pintype "bidirectional"))
    )
    (net (code "248") (name "unconnected-(CON2-Pad144)") (class "Default")
      (node (ref "CON2") (pin "144") (pinfunction "144_144") (pintype "bidirectional"))
    )
    (net (code "249") (name "unconnected-(CON2-Pad145)") (class "Default")
      (node (ref "CON2") (pin "145") (pinfunction "145_145") (pintype "bidirectional"))
    )
    (net (code "250") (name "unconnected-(CON2-Pad146)") (class "Default")
      (node (ref "CON2") (pin "146") (pinfunction "146_146") (pintype "bidirectional"))
    )
    (net (code "251") (name "unconnected-(CON2-Pad147)") (class "Default")
      (node (ref "CON2") (pin "147") (pinfunction "147_147") (pintype "bidirectional"))
    )
    (net (code "252") (name "unconnected-(CON2-Pad148)") (class "Default")
      (node (ref "CON2") (pin "148") (pinfunction "148_148") (pintype "bidirectional"))
    )
    (net (code "253") (name "unconnected-(CON2-Pad149)") (class "Default")
      (node (ref "CON2") (pin "149") (pinfunction "149_149") (pintype "bidirectional"))
    )
    (net (code "254") (name "unconnected-(CON2-Pad150)") (class "Default")
      (node (ref "CON2") (pin "150") (pinfunction "150_150") (pintype "bidirectional"))
    )
    (net (code "255") (name "unconnected-(CON2-Pad151)") (class "Default")
      (node (ref "CON2") (pin "151") (pinfunction "151_151") (pintype "bidirectional"))
    )
    (net (code "256") (name "unconnected-(CON2-Pad152)") (class "Default")
      (node (ref "CON2") (pin "152") (pinfunction "152_152") (pintype "bidirectional"))
    )
    (net (code "257") (name "unconnected-(CON2-Pad153)") (class "Default")
      (node (ref "CON2") (pin "153") (pinfunction "153_153") (pintype "bidirectional"))
    )
    (net (code "258") (name "unconnected-(CON2-Pad154)") (class "Default")
      (node (ref "CON2") (pin "154") (pinfunction "154_154") (pintype "bidirectional"))
    )
    (net (code "259") (name "unconnected-(CON2-Pad155)") (class "Default")
      (node (ref "CON2") (pin "155") (pinfunction "155_155") (pintype "bidirectional"))
    )
    (net (code "260") (name "unconnected-(CON2-Pad156)") (class "Default")
      (node (ref "CON2") (pin "156") (pinfunction "156_156") (pintype "bidirectional"))
    )
    (net (code "261") (name "unconnected-(CON2-Pad157)") (class "Default")
      (node (ref "CON2") (pin "157") (pinfunction "157_157") (pintype "bidirectional"))
    )
    (net (code "262") (name "unconnected-(CON2-Pad158)") (class "Default")
      (node (ref "CON2") (pin "158") (pinfunction "158_158") (pintype "bidirectional"))
    )
    (net (code "263") (name "unconnected-(CON2-Pad159)") (class "Default")
      (node (ref "CON2") (pin "159") (pinfunction "159_159") (pintype "bidirectional"))
    )
    (net (code "264") (name "unconnected-(CON2-Pad160)") (class "Default")
      (node (ref "CON2") (pin "160") (pinfunction "160_160") (pintype "bidirectional"))
    )
    (net (code "265") (name "unconnected-(CON2-Pad161)") (class "Default")
      (node (ref "CON2") (pin "161") (pinfunction "161_161") (pintype "bidirectional"))
    )
    (net (code "266") (name "unconnected-(CON2-Pad162)") (class "Default")
      (node (ref "CON2") (pin "162") (pinfunction "162_162") (pintype "bidirectional"))
    )
  )
)
